# L6790A_Si.net
KiCad netlist of a schematic drawn in Altium Designer
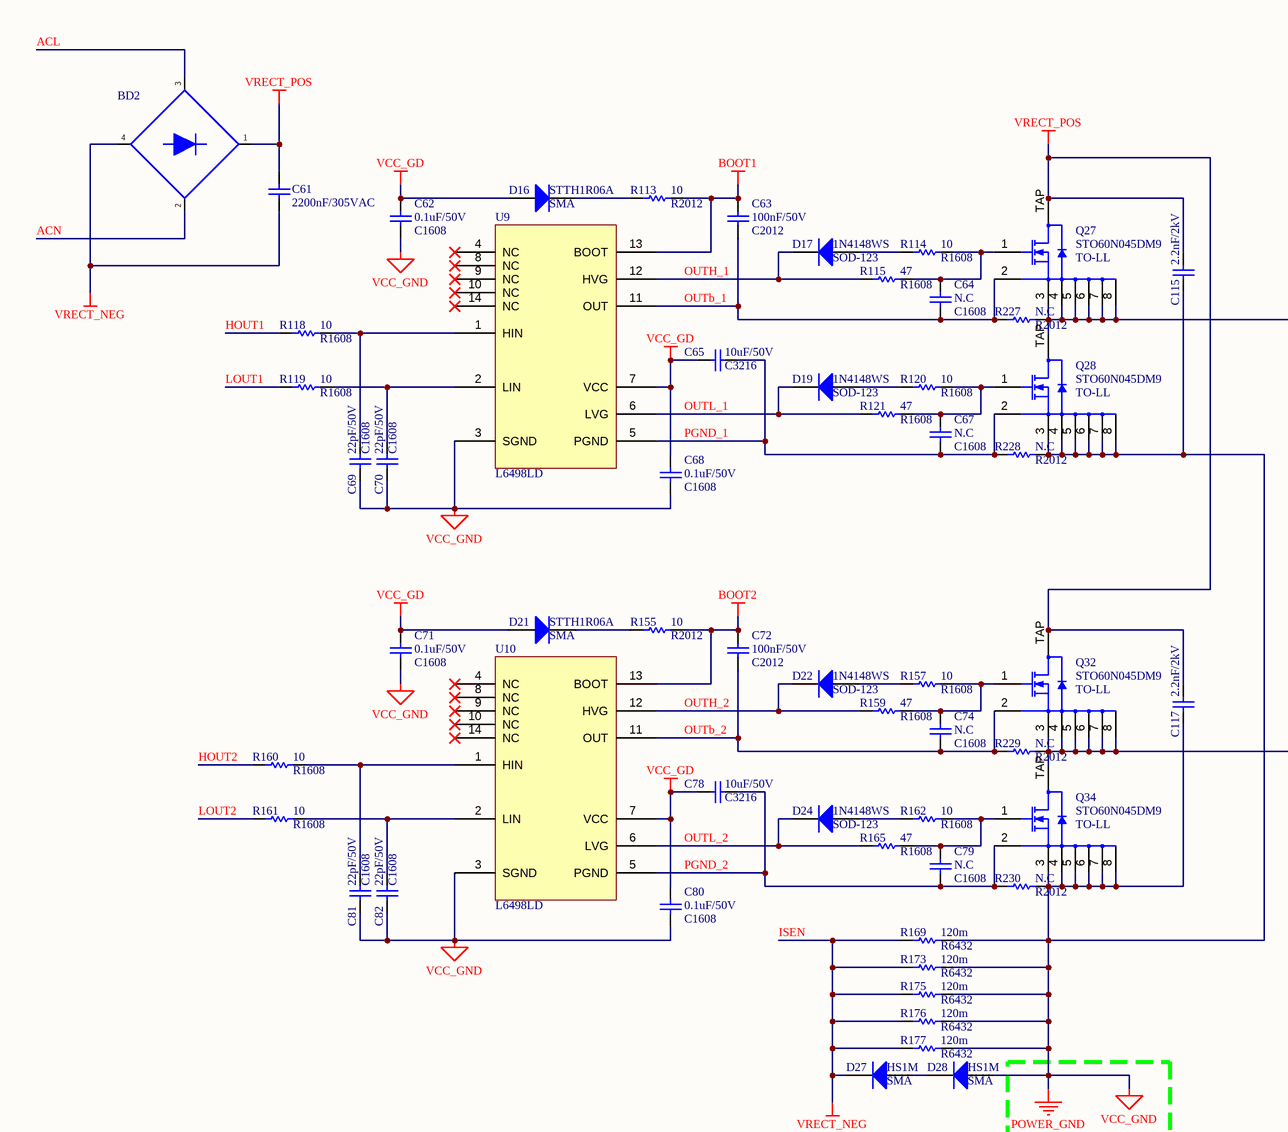
[diagram p0: L6790A_Si.SchDoc, top left]
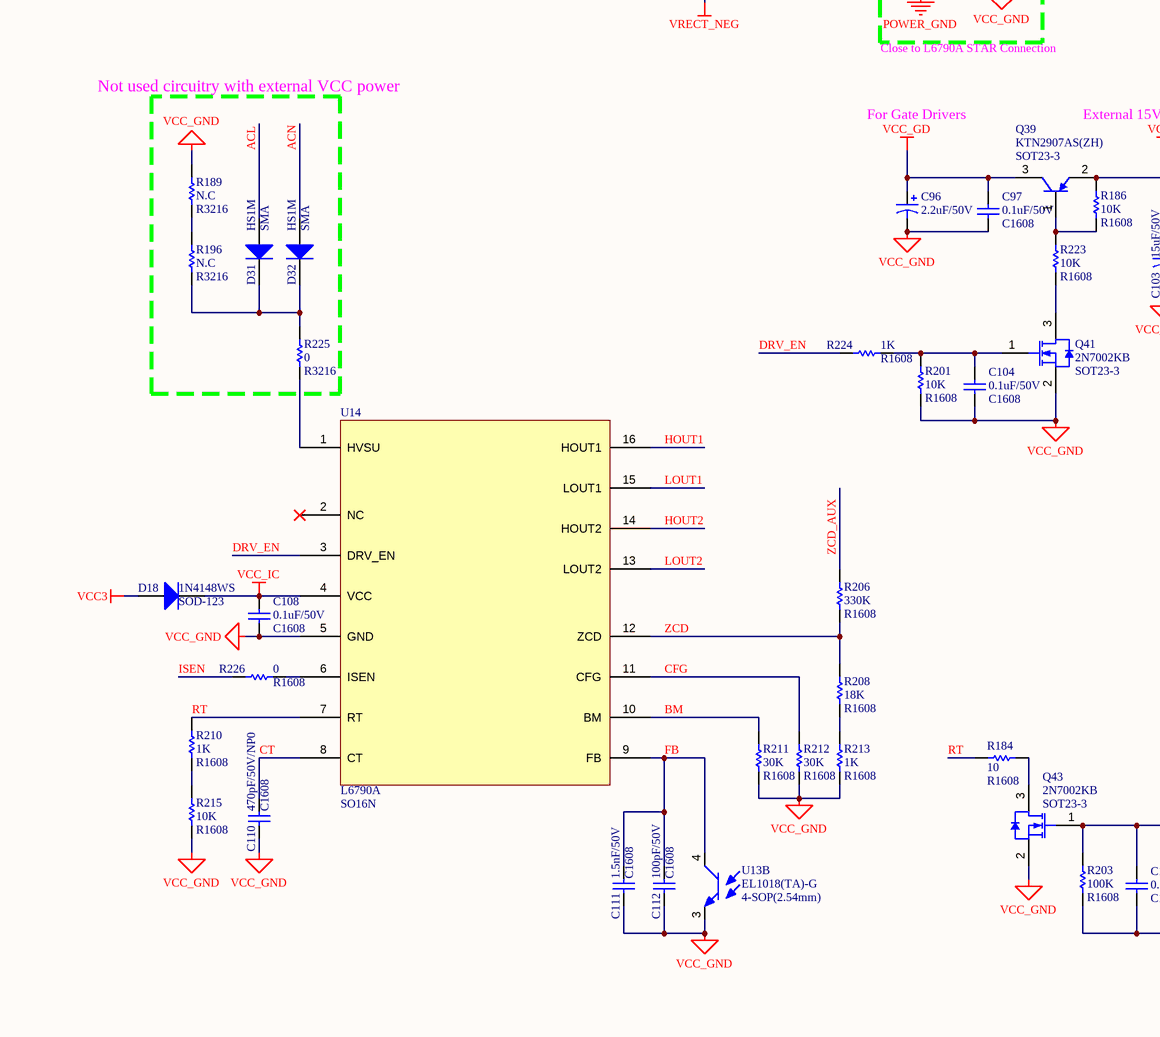
[diagram p1: L6790A_Si.SchDoc, bottom left]
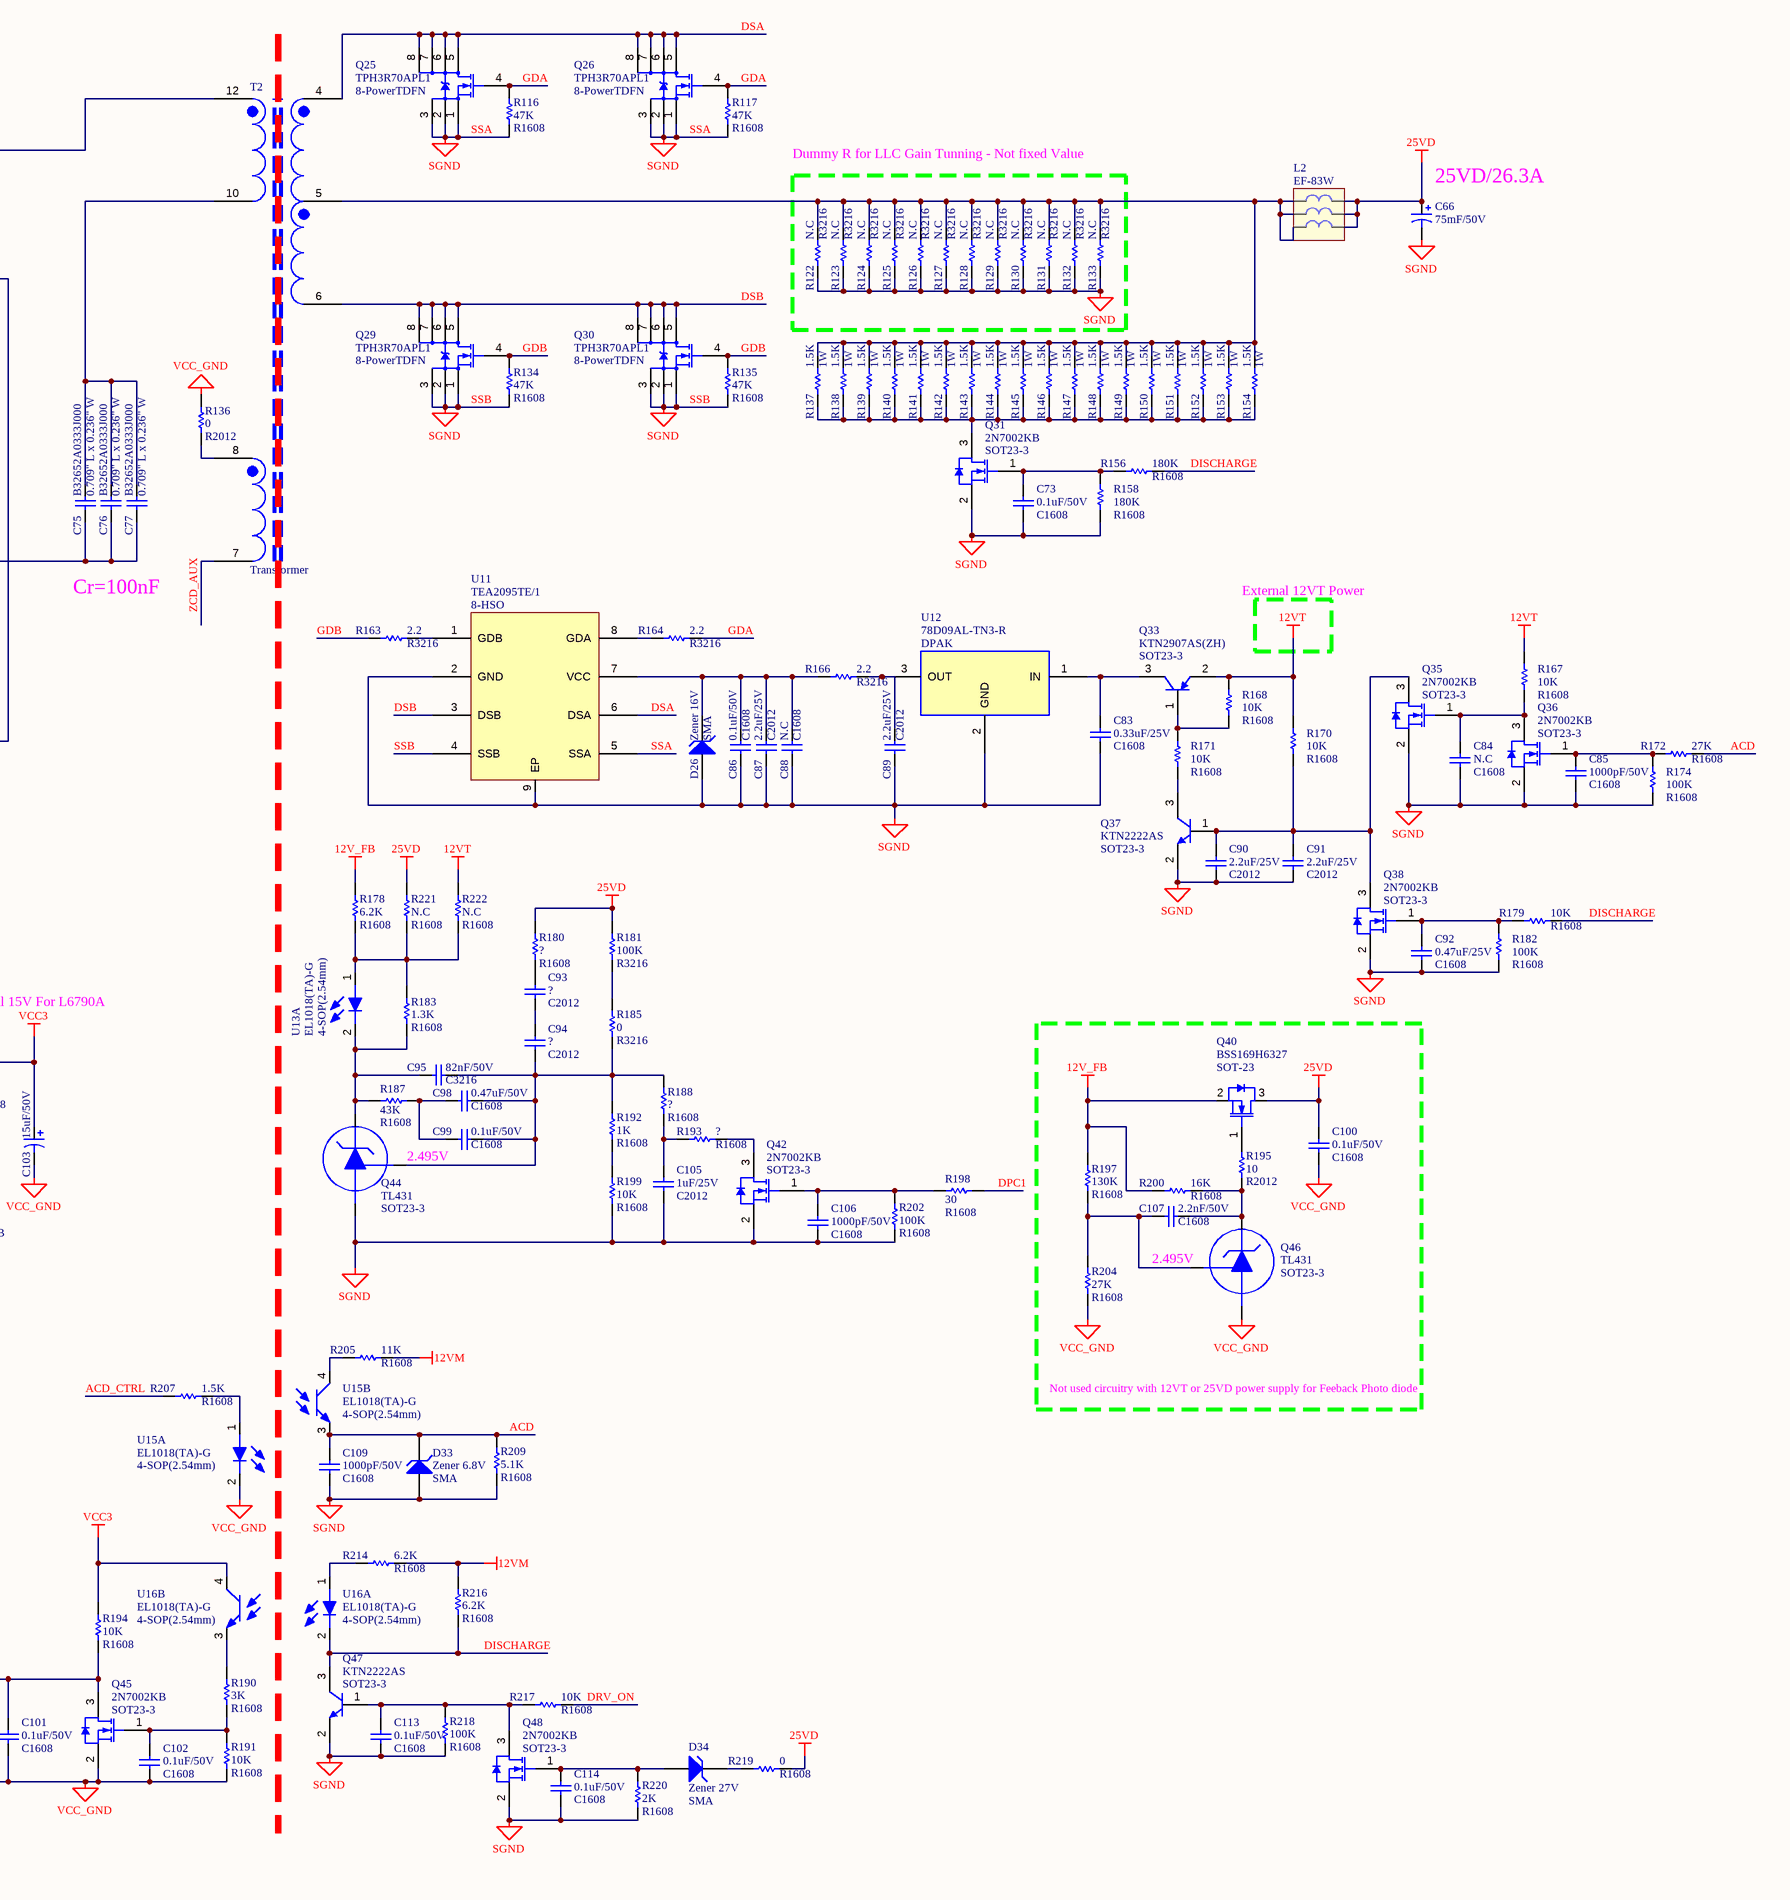
[diagram p2: L6790A_Si.SchDoc, bottom right]

(export (version "E")
  (design (tool "Eeschema 10.0.6"))
  (components
    (comp (ref "BD2")
      (value "TS6KL60")
      (footprint "2W-DIO-MI-4L-4_6X25X15-7_5P-BD")
      (description "BRIDGE DIODE")
      (libsource (lib "Schematic") (part "BRIDGE"))
    )
    (comp (ref "C61")
      (value "2200nF/305VAC")
      (description "Chip MLCC")
      (libsource (lib "Miscellaneous Devices") (part "Cap"))
    )
    (comp (ref "C62")
      (value "0.1uF/50V")
      (description "Chip MLCC")
      (fields (field (name "PACKAGE/CASE") "C1608"))
      (libsource (lib "Miscellaneous Devices") (part "Cap"))
    )
    (comp (ref "C63")
      (value "100nF/50V")
      (description "Chip MLCC")
      (fields (field (name "PACKAGE/CASE") "C2012"))
      (libsource (lib "Miscellaneous Devices") (part "Cap"))
    )
    (comp (ref "C64")
      (value "N.C")
      (description "Chip MLCC")
      (fields (field (name "PACKAGE/CASE") "C1608"))
      (libsource (lib "Miscellaneous Devices") (part "Cap"))
    )
    (comp (ref "C65")
      (value "10uF/50V")
      (description "Chip MLCC")
      (fields (field (name "PACKAGE/CASE") "C3216"))
      (libsource (lib "Miscellaneous Devices") (part "Cap"))
    )
    (comp (ref "C66")
      (value "75mF/50V")
      (footprint "1W-CAP-MI-2L-16DX25-7_5P-EL-F-R1212")
      (description "Electrolytic Capacitor")
      (libsource (lib "Miscellaneous Devices") (part "Cap Pol1"))
    )
    (comp (ref "C67")
      (value "N.C")
      (description "Chip MLCC")
      (fields (field (name "PACKAGE/CASE") "C1608"))
      (libsource (lib "Miscellaneous Devices") (part "Cap"))
    )
    (comp (ref "C68")
      (value "0.1uF/50V")
      (description "Chip MLCC")
      (fields (field (name "PACKAGE/CASE") "C1608"))
      (libsource (lib "Miscellaneous Devices") (part "Cap"))
    )
    (comp (ref "C69")
      (value "22pF/50V")
      (description "Chip MLCC")
      (fields (field (name "PACKAGE/CASE") "C1608"))
      (libsource (lib "Miscellaneous Devices") (part "Cap"))
    )
    (comp (ref "C70")
      (value "22pF/50V")
      (description "Chip MLCC")
      (fields (field (name "PACKAGE/CASE") "C1608"))
      (libsource (lib "Miscellaneous Devices") (part "Cap"))
    )
    (comp (ref "C71")
      (value "0.1uF/50V")
      (description "Chip MLCC")
      (fields (field (name "PACKAGE/CASE") "C1608"))
      (libsource (lib "Miscellaneous Devices") (part "Cap"))
    )
    (comp (ref "C72")
      (value "100nF/50V")
      (description "Chip MLCC")
      (fields (field (name "PACKAGE/CASE") "C2012"))
      (libsource (lib "Miscellaneous Devices") (part "Cap"))
    )
    (comp (ref "C73")
      (value "0.1uF/50V")
      (description "Chip MLCC")
      (fields (field (name "PACKAGE/CASE") "C1608"))
      (libsource (lib "Miscellaneous Devices") (part "Cap"))
    )
    (comp (ref "C74")
      (value "N.C")
      (description "Chip MLCC")
      (fields (field (name "PACKAGE/CASE") "C1608"))
      (libsource (lib "Miscellaneous Devices") (part "Cap"))
    )
    (comp (ref "C75")
      (value "B32652A0333J000")
      (description "Chip MLCC")
      (fields (field (name "PACKAGE/CASE") "0.709\" L x 0.236\" W"))
      (libsource (lib "Miscellaneous Devices") (part "Cap"))
    )
    (comp (ref "C76")
      (value "B32652A0333J000")
      (description "Chip MLCC")
      (fields (field (name "PACKAGE/CASE") "0.709\" L x 0.236\" W"))
      (libsource (lib "Miscellaneous Devices") (part "Cap"))
    )
    (comp (ref "C77")
      (value "B32652A0333J000")
      (description "Chip MLCC")
      (fields (field (name "PACKAGE/CASE") "0.709\" L x 0.236\" W"))
      (libsource (lib "Miscellaneous Devices") (part "Cap"))
    )
    (comp (ref "C78")
      (value "10uF/50V")
      (description "Chip MLCC")
      (fields (field (name "PACKAGE/CASE") "C3216"))
      (libsource (lib "Miscellaneous Devices") (part "Cap"))
    )
    (comp (ref "C79")
      (value "N.C")
      (description "Chip MLCC")
      (fields (field (name "PACKAGE/CASE") "C1608"))
      (libsource (lib "Miscellaneous Devices") (part "Cap"))
    )
    (comp (ref "C80")
      (value "0.1uF/50V")
      (description "Chip MLCC")
      (fields (field (name "PACKAGE/CASE") "C1608"))
      (libsource (lib "Miscellaneous Devices") (part "Cap"))
    )
    (comp (ref "C81")
      (value "22pF/50V")
      (description "Chip MLCC")
      (fields (field (name "PACKAGE/CASE") "C1608"))
      (libsource (lib "Miscellaneous Devices") (part "Cap"))
    )
    (comp (ref "C82")
      (value "22pF/50V")
      (description "Chip MLCC")
      (fields (field (name "PACKAGE/CASE") "C1608"))
      (libsource (lib "Miscellaneous Devices") (part "Cap"))
    )
    (comp (ref "C83")
      (value "0.33uF/25V")
      (description "Chip MLCC")
      (fields (field (name "PACKAGE/CASE") "C1608"))
      (libsource (lib "Miscellaneous Devices") (part "Cap"))
    )
    (comp (ref "C84")
      (value "N.C")
      (description "Chip MLCC")
      (fields (field (name "PACKAGE/CASE") "C1608"))
      (libsource (lib "Miscellaneous Devices") (part "Cap"))
    )
    (comp (ref "C85")
      (value "1000pF/50V")
      (description "Chip MLCC")
      (fields (field (name "PACKAGE/CASE") "C1608"))
      (libsource (lib "Miscellaneous Devices") (part "Cap"))
    )
    (comp (ref "C86")
      (value "0.1uF/50V")
      (description "Chip MLCC")
      (fields (field (name "PACKAGE/CASE") "C1608"))
      (libsource (lib "Miscellaneous Devices") (part "Cap"))
    )
    (comp (ref "C87")
      (value "2.2uF/25V")
      (description "Chip MLCC")
      (fields (field (name "PACKAGE/CASE") "C2012"))
      (libsource (lib "Miscellaneous Devices") (part "Cap"))
    )
    (comp (ref "C88")
      (value "N.C")
      (description "Chip MLCC")
      (fields (field (name "PACKAGE/CASE") "C1608"))
      (libsource (lib "Miscellaneous Devices") (part "Cap"))
    )
    (comp (ref "C89")
      (value "2.2uF/25V")
      (description "Chip MLCC")
      (fields (field (name "PACKAGE/CASE") "C2012"))
      (libsource (lib "Miscellaneous Devices") (part "Cap"))
    )
    (comp (ref "C90")
      (value "2.2uF/25V")
      (description "Chip MLCC")
      (fields (field (name "PACKAGE/CASE") "C2012"))
      (libsource (lib "Miscellaneous Devices") (part "Cap"))
    )
    (comp (ref "C91")
      (value "2.2uF/25V")
      (description "Chip MLCC")
      (fields (field (name "PACKAGE/CASE") "C2012"))
      (libsource (lib "Miscellaneous Devices") (part "Cap"))
    )
    (comp (ref "C92")
      (value "0.47uF/25V")
      (description "Chip MLCC")
      (fields (field (name "PACKAGE/CASE") "C1608"))
      (libsource (lib "Miscellaneous Devices") (part "Cap"))
    )
    (comp (ref "C93")
      (value "?")
      (description "Chip MLCC")
      (fields (field (name "PACKAGE/CASE") "C2012"))
      (libsource (lib "Miscellaneous Devices") (part "Cap"))
    )
    (comp (ref "C94")
      (value "?")
      (description "Chip MLCC")
      (fields (field (name "PACKAGE/CASE") "C2012"))
      (libsource (lib "Miscellaneous Devices") (part "Cap"))
    )
    (comp (ref "C95")
      (value "82nF/50V")
      (footprint "LGP55B_25U1_Y2S:CAP-CHP-3216-R0")
      (description "Chip MLCC")
      (fields (field (name "PACKAGE/CASE") "C3216"))
      (libsource (lib "Miscellaneous Devices") (part "Cap"))
    )
    (comp (ref "C96")
      (value "2.2uF/50V")
      (footprint "CAP-RA-D5.0H12_5-P2-R0CA")
      (description "Electrolytic Capacitor 33uF/25V")
      (libsource (lib "Miscellaneous Devices") (part "Cap Pol1"))
    )
    (comp (ref "C97")
      (value "0.1uF/50V")
      (description "Chip MLCC")
      (fields (field (name "PACKAGE/CASE") "C1608"))
      (libsource (lib "Miscellaneous Devices") (part "Cap"))
    )
    (comp (ref "C98")
      (value "0.47uF/50V")
      (description "Chip MLCC")
      (fields (field (name "PACKAGE/CASE") "C1608"))
      (libsource (lib "Miscellaneous Devices") (part "Cap"))
    )
    (comp (ref "C99")
      (value "0.1uF/50V")
      (description "Chip MLCC")
      (fields (field (name "PACKAGE/CASE") "C1608"))
      (libsource (lib "Miscellaneous Devices") (part "Cap"))
    )
    (comp (ref "C100")
      (value "0.1uF/50V")
      (description "Chip MLCC")
      (fields (field (name "PACKAGE/CASE") "C1608"))
      (libsource (lib "Miscellaneous Devices") (part "Cap"))
    )
    (comp (ref "C101")
      (value "0.1uF/50V")
      (description "Chip MLCC")
      (fields (field (name "PACKAGE/CASE") "C1608"))
      (libsource (lib "Miscellaneous Devices") (part "Cap"))
    )
    (comp (ref "C102")
      (value "0.1uF/50V")
      (description "Chip MLCC")
      (fields (field (name "PACKAGE/CASE") "C1608"))
      (libsource (lib "Miscellaneous Devices") (part "Cap"))
    )
    (comp (ref "C103")
      (value "15uF/50V")
      (footprint "CAP-RA-D5.0H12_5-P2-R0CA")
      (description "Electrolytic Capacitor 33uF/25V")
      (libsource (lib "Miscellaneous Devices") (part "Cap Pol1"))
    )
    (comp (ref "C104")
      (value "0.1uF/50V")
      (description "Chip MLCC")
      (fields (field (name "PACKAGE/CASE") "C1608"))
      (libsource (lib "Miscellaneous Devices") (part "Cap"))
    )
    (comp (ref "C105")
      (value "1uF/25V")
      (description "Chip MLCC")
      (fields (field (name "PACKAGE/CASE") "C2012"))
      (libsource (lib "Miscellaneous Devices") (part "Cap"))
    )
    (comp (ref "C106")
      (value "1000pF/50V")
      (description "Chip MLCC")
      (fields (field (name "PACKAGE/CASE") "C1608"))
      (libsource (lib "Miscellaneous Devices") (part "Cap"))
    )
    (comp (ref "C107")
      (value "2.2nF/50V")
      (description "Chip MLCC")
      (fields (field (name "PACKAGE/CASE") "C1608"))
      (libsource (lib "Miscellaneous Devices") (part "Cap"))
    )
    (comp (ref "C108")
      (value "0.1uF/50V")
      (description "Chip MLCC")
      (fields (field (name "PACKAGE/CASE") "C1608"))
      (libsource (lib "Miscellaneous Devices") (part "Cap"))
    )
    (comp (ref "C109")
      (value "1000pF/50V")
      (description "Chip MLCC")
      (fields (field (name "PACKAGE/CASE") "C1608"))
      (libsource (lib "Miscellaneous Devices") (part "Cap"))
    )
    (comp (ref "C110")
      (value "470pF/50V/NP0")
      (description "Chip MLCC")
      (fields (field (name "PACKAGE/CASE") "C1608"))
      (libsource (lib "Miscellaneous Devices") (part "Cap"))
    )
    (comp (ref "C111")
      (value "1.5nF/50V")
      (description "Chip MLCC")
      (fields (field (name "PACKAGE/CASE") "C1608"))
      (libsource (lib "Miscellaneous Devices") (part "Cap"))
    )
    (comp (ref "C112")
      (value "100pF/50V")
      (description "Chip MLCC")
      (fields (field (name "PACKAGE/CASE") "C1608"))
      (libsource (lib "Miscellaneous Devices") (part "Cap"))
    )
    (comp (ref "C113")
      (value "0.1uF/50V")
      (description "Chip MLCC")
      (fields (field (name "PACKAGE/CASE") "C1608"))
      (libsource (lib "Miscellaneous Devices") (part "Cap"))
    )
    (comp (ref "C114")
      (value "0.1uF/50V")
      (description "Chip MLCC")
      (fields (field (name "PACKAGE/CASE") "C1608"))
      (libsource (lib "Miscellaneous Devices") (part "Cap"))
    )
    (comp (ref "C115")
      (value "2.2nF/2kV")
      (description "Chip MLCC")
      (libsource (lib "Miscellaneous Devices") (part "Cap"))
    )
    (comp (ref "C117")
      (value "2.2nF/2kV")
      (description "Chip MLCC")
      (libsource (lib "Miscellaneous Devices") (part "Cap"))
    )
    (comp (ref "D16")
      (value "STTH1R06A")
      (footprint "DIO-SOD123")
      (description "DIODE SCHOTTKY 30V 200MA SOD123")
      (fields (field (name "PACKAGE/CASE") "SMA"))
      (libsource (lib "Miscellaneous Devices") (part "Diode 1N4148"))
    )
    (comp (ref "D17")
      (value "1N4148WS")
      (footprint "DIO-SOD123")
      (description "DIODE SCHOTTKY 30V 200MA SOD123")
      (fields (field (name "PACKAGE/CASE") "SOD-123"))
      (libsource (lib "Miscellaneous Devices") (part "Diode 1N4148"))
    )
    (comp (ref "D18")
      (value "1N4148WS")
      (footprint "DIO-SOD123")
      (description "DIODE SCHOTTKY 30V 200MA SOD123")
      (fields (field (name "PACKAGE/CASE") "SOD-123"))
      (libsource (lib "Miscellaneous Devices") (part "Diode 1N4148"))
    )
    (comp (ref "D19")
      (value "1N4148WS")
      (footprint "DIO-SOD123")
      (description "DIODE SCHOTTKY 30V 200MA SOD123")
      (fields (field (name "PACKAGE/CASE") "SOD-123"))
      (libsource (lib "Miscellaneous Devices") (part "Diode 1N4148"))
    )
    (comp (ref "D21")
      (value "STTH1R06A")
      (footprint "DIO-SOD123")
      (description "DIODE SCHOTTKY 30V 200MA SOD123")
      (fields (field (name "PACKAGE/CASE") "SMA"))
      (libsource (lib "Miscellaneous Devices") (part "Diode 1N4148"))
    )
    (comp (ref "D22")
      (value "1N4148WS")
      (footprint "DIO-SOD123")
      (description "DIODE SCHOTTKY 30V 200MA SOD123")
      (fields (field (name "PACKAGE/CASE") "SOD-123"))
      (libsource (lib "Miscellaneous Devices") (part "Diode 1N4148"))
    )
    (comp (ref "D24")
      (value "1N4148WS")
      (footprint "DIO-SOD123")
      (description "DIODE SCHOTTKY 30V 200MA SOD123")
      (fields (field (name "PACKAGE/CASE") "SOD-123"))
      (libsource (lib "Miscellaneous Devices") (part "Diode 1N4148"))
    )
    (comp (ref "D26")
      (value "Zener 16V")
      (footprint "1W-DIO-CHP-2L-SOD106-SMA")
      (description "DIODE ZENER 30V 1W DO214AC")
      (fields (field (name "PACKAGE/CASE") "SMA"))
      (libsource (lib "Miscellaneous Devices") (part "D Zener"))
    )
    (comp (ref "D27")
      (value "HS1M")
      (footprint "DIO-SOD123")
      (description "DIODE SCHOTTKY 30V 200MA SOD123")
      (fields (field (name "PACKAGE/CASE") "SMA"))
      (libsource (lib "Miscellaneous Devices") (part "Diode 1N4148"))
    )
    (comp (ref "D28")
      (value "HS1M")
      (footprint "DIO-SOD123")
      (description "DIODE SCHOTTKY 30V 200MA SOD123")
      (fields (field (name "PACKAGE/CASE") "SMA"))
      (libsource (lib "Miscellaneous Devices") (part "Diode 1N4148"))
    )
    (comp (ref "D31")
      (value "HS1M")
      (footprint "DIO-SOD123")
      (description "DIODE SCHOTTKY 30V 200MA SOD123")
      (fields (field (name "PACKAGE/CASE") "SMA"))
      (libsource (lib "Miscellaneous Devices") (part "Diode 1N4148"))
    )
    (comp (ref "D32")
      (value "HS1M")
      (footprint "DIO-SOD123")
      (description "DIODE SCHOTTKY 30V 200MA SOD123")
      (fields (field (name "PACKAGE/CASE") "SMA"))
      (libsource (lib "Miscellaneous Devices") (part "Diode 1N4148"))
    )
    (comp (ref "D33")
      (value "Zener 6.8V")
      (footprint "1W-DIO-CHP-2L-SOD106-SMA")
      (description "DIODE ZENER 30V 1W DO214AC")
      (fields (field (name "PACKAGE/CASE") "SMA"))
      (libsource (lib "Miscellaneous Devices") (part "D Zener"))
    )
    (comp (ref "D34")
      (value "Zener 27V")
      (footprint "1W-DIO-CHP-2L-SOD106-SMA")
      (description "DIODE ZENER 30V 1W DO214AC")
      (fields (field (name "PACKAGE/CASE") "SMA"))
      (libsource (lib "Miscellaneous Devices") (part "D Zener"))
    )
    (comp (ref "L2") (value "EF-83W") (libsource (lib "Schematic") (part "EF-83W")))
    (comp (ref "Q25")
      (value "TPH3R70APL1")
      (description "N-Channel 100 V 90A (Tc) 210W (Tc) Surface Mount 8-SOP Advance (5x5.75)")
      (fields (field (name "PACKAGE/CASE") "8-PowerTDFN"))
      (libsource (lib "Schematic") (part "TPH3R70APL1"))
    )
    (comp (ref "Q26")
      (value "TPH3R70APL1")
      (description "N-Channel 100 V 90A (Tc) 210W (Tc) Surface Mount 8-SOP Advance (5x5.75)")
      (fields (field (name "PACKAGE/CASE") "8-PowerTDFN"))
      (libsource (lib "Schematic") (part "TPH3R70APL1"))
    )
    (comp (ref "Q27")
      (value "STO60N045DM9")
      (description "N‑channel 600 V, 35 mΩ typ., 56 A MDmesh DM9 Power MOSFET in a TO‑LL package")
      (fields (field (name "PACKAGE/CASE") "TO-LL"))
      (libsource (lib "Schematic") (part "STO60N045DM9"))
    )
    (comp (ref "Q28")
      (value "STO60N045DM9")
      (description "N‑channel 600 V, 35 mΩ typ., 56 A MDmesh DM9 Power MOSFET in a TO‑LL package")
      (fields (field (name "PACKAGE/CASE") "TO-LL"))
      (libsource (lib "Schematic") (part "STO60N045DM9"))
    )
    (comp (ref "Q29")
      (value "TPH3R70APL1")
      (description "N-Channel 100 V 90A (Tc) 210W (Tc) Surface Mount 8-SOP Advance (5x5.75)")
      (fields (field (name "PACKAGE/CASE") "8-PowerTDFN"))
      (libsource (lib "Schematic") (part "TPH3R70APL1"))
    )
    (comp (ref "Q30")
      (value "TPH3R70APL1")
      (description "N-Channel 100 V 90A (Tc) 210W (Tc) Surface Mount 8-SOP Advance (5x5.75)")
      (fields (field (name "PACKAGE/CASE") "8-PowerTDFN"))
      (libsource (lib "Schematic") (part "TPH3R70APL1"))
    )
    (comp (ref "Q31")
      (value "2N7002KB")
      (description "N-CH MOSFET")
      (fields (field (name "PACKAGE/CASE") "SOT23-3"))
      (libsource (lib "Schematic") (part "2N7002KB"))
    )
    (comp (ref "Q32")
      (value "STO60N045DM9")
      (description "N‑channel 600 V, 35 mΩ typ., 56 A MDmesh DM9 Power MOSFET in a TO‑LL package")
      (fields (field (name "PACKAGE/CASE") "TO-LL"))
      (libsource (lib "Schematic") (part "STO60N045DM9"))
    )
    (comp (ref "Q33")
      (value "KTN2907AS(ZH)")
      (description "PNP BJT")
      (fields (field (name "PACKAGE/CASE") "SOT23-3"))
      (libsource (lib "Schematic") (part "ONSC-PNP-B1E2C3-3"))
    )
    (comp (ref "Q34")
      (value "STO60N045DM9")
      (description "N‑channel 600 V, 35 mΩ typ., 56 A MDmesh DM9 Power MOSFET in a TO‑LL package")
      (fields (field (name "PACKAGE/CASE") "TO-LL"))
      (libsource (lib "Schematic") (part "STO60N045DM9"))
    )
    (comp (ref "Q35")
      (value "2N7002KB")
      (description "N-CH MOSFET")
      (fields (field (name "PACKAGE/CASE") "SOT23-3"))
      (libsource (lib "Schematic") (part "2N7002KB"))
    )
    (comp (ref "Q36")
      (value "2N7002KB")
      (description "N-CH MOSFET")
      (fields (field (name "PACKAGE/CASE") "SOT23-3"))
      (libsource (lib "Schematic") (part "2N7002KB"))
    )
    (comp (ref "Q37")
      (value "KTN2222AS")
      (description "BJT NPN")
      (fields (field (name "PACKAGE/CASE") "SOT23-3"))
      (libsource (lib "Schematic") (part "ONSC-NPN-B1E2C3-3"))
    )
    (comp (ref "Q38")
      (value "2N7002KB")
      (description "N-CH MOSFET")
      (fields (field (name "PACKAGE/CASE") "SOT23-3"))
      (libsource (lib "Schematic") (part "2N7002KB"))
    )
    (comp (ref "Q39")
      (value "KTN2907AS(ZH)")
      (description "PNP BJT")
      (fields (field (name "PACKAGE/CASE") "SOT23-3"))
      (libsource (lib "Schematic") (part "ONSC-PNP-B1E2C3-3"))
    )
    (comp (ref "Q40")
      (value "BSS169H6327")
      (footprint "SOT-23_TR")
      (description "MOSFET N-CH 100V 170MA SOT23-3")
      (fields (field (name "PACKAGE/CASE") "SOT-23"))
      (libsource (lib "Miscellaneous Devices") (part "CMP-32901-000982-1"))
    )
    (comp (ref "Q41")
      (value "2N7002KB")
      (description "N-CH MOSFET")
      (fields (field (name "PACKAGE/CASE") "SOT23-3"))
      (libsource (lib "Schematic") (part "2N7002KB"))
    )
    (comp (ref "Q42")
      (value "2N7002KB")
      (description "N-CH MOSFET")
      (fields (field (name "PACKAGE/CASE") "SOT23-3"))
      (libsource (lib "Schematic") (part "2N7002KB"))
    )
    (comp (ref "Q43")
      (value "2N7002KB")
      (description "N-CH MOSFET")
      (fields (field (name "PACKAGE/CASE") "SOT23-3"))
      (libsource (lib "Schematic") (part "2N7002KB"))
    )
    (comp (ref "Q44")
      (value "TL431")
      (footprint "SOT-23_TR")
      (description "IC VREF SHUNT ADJ 1% SOT23-3")
      (fields (field (name "PACKAGE/CASE") "SOT23-3"))
      (libsource (lib "*") (part "1W-IC-CHP-3L-SOT23-SCR-R0"))
    )
    (comp (ref "Q45")
      (value "2N7002KB")
      (description "N-CH MOSFET")
      (fields (field (name "PACKAGE/CASE") "SOT23-3"))
      (libsource (lib "Schematic") (part "2N7002KB"))
    )
    (comp (ref "Q46")
      (value "TL431")
      (footprint "SOT-23_TR")
      (description "IC VREF SHUNT ADJ 1% SOT23-3")
      (fields (field (name "PACKAGE/CASE") "SOT23-3"))
      (libsource (lib "*") (part "1W-IC-CHP-3L-SOT23-SCR-R0"))
    )
    (comp (ref "Q47")
      (value "KTN2222AS")
      (description "BJT NPN")
      (fields (field (name "PACKAGE/CASE") "SOT23-3"))
      (libsource (lib "Schematic") (part "ONSC-NPN-B1E2C3-3"))
    )
    (comp (ref "Q48")
      (value "2N7002KB")
      (description "N-CH MOSFET")
      (fields (field (name "PACKAGE/CASE") "SOT23-3"))
      (libsource (lib "Schematic") (part "2N7002KB"))
    )
    (comp (ref "R113")
      (value "10")
      (footprint "RES-1608")
      (description "Chip Resistor")
      (fields (field (name "PACKAGE/CASE") "R2012"))
      (libsource (lib "Miscellaneous Devices") (part "Res1"))
    )
    (comp (ref "R114")
      (value "10")
      (footprint "RES-1608")
      (description "Chip Resistor")
      (fields (field (name "PACKAGE/CASE") "R1608"))
      (libsource (lib "Miscellaneous Devices") (part "Res1"))
    )
    (comp (ref "R115")
      (value "47")
      (footprint "RES-1608")
      (description "Chip Resistor")
      (fields (field (name "PACKAGE/CASE") "R1608"))
      (libsource (lib "Miscellaneous Devices") (part "Res1"))
    )
    (comp (ref "R116")
      (value "47K")
      (footprint "RES-1608")
      (description "Chip Resistor")
      (fields (field (name "PACKAGE/CASE") "R1608"))
      (libsource (lib "Miscellaneous Devices") (part "Res1"))
    )
    (comp (ref "R117")
      (value "47K")
      (footprint "RES-1608")
      (description "Chip Resistor")
      (fields (field (name "PACKAGE/CASE") "R1608"))
      (libsource (lib "Miscellaneous Devices") (part "Res1"))
    )
    (comp (ref "R118")
      (value "10")
      (footprint "RES-1608")
      (description "Chip Resistor")
      (fields (field (name "PACKAGE/CASE") "R1608"))
      (libsource (lib "Miscellaneous Devices") (part "Res1"))
    )
    (comp (ref "R119")
      (value "10")
      (footprint "RES-1608")
      (description "Chip Resistor")
      (fields (field (name "PACKAGE/CASE") "R1608"))
      (libsource (lib "Miscellaneous Devices") (part "Res1"))
    )
    (comp (ref "R120")
      (value "10")
      (footprint "RES-1608")
      (description "Chip Resistor")
      (fields (field (name "PACKAGE/CASE") "R1608"))
      (libsource (lib "Miscellaneous Devices") (part "Res1"))
    )
    (comp (ref "R121")
      (value "47")
      (footprint "RES-1608")
      (description "Chip Resistor")
      (fields (field (name "PACKAGE/CASE") "R1608"))
      (libsource (lib "Miscellaneous Devices") (part "Res1"))
    )
    (comp (ref "R122")
      (value "N.C")
      (footprint "RES-3216")
      (description "Chip Resistor")
      (fields (field (name "PACKAGE/CASE") "R3216"))
      (libsource (lib "Miscellaneous Devices") (part "Res1"))
    )
    (comp (ref "R123")
      (value "N.C")
      (footprint "RES-3216")
      (description "Chip Resistor")
      (fields (field (name "PACKAGE/CASE") "R3216"))
      (libsource (lib "Miscellaneous Devices") (part "Res1"))
    )
    (comp (ref "R124")
      (value "N.C")
      (footprint "RES-3216")
      (description "Chip Resistor")
      (fields (field (name "PACKAGE/CASE") "R3216"))
      (libsource (lib "Miscellaneous Devices") (part "Res1"))
    )
    (comp (ref "R125")
      (value "N.C")
      (footprint "RES-3216")
      (description "Chip Resistor")
      (fields (field (name "PACKAGE/CASE") "R3216"))
      (libsource (lib "Miscellaneous Devices") (part "Res1"))
    )
    (comp (ref "R126")
      (value "N.C")
      (footprint "RES-3216")
      (description "Chip Resistor")
      (fields (field (name "PACKAGE/CASE") "R3216"))
      (libsource (lib "Miscellaneous Devices") (part "Res1"))
    )
    (comp (ref "R127")
      (value "N.C")
      (footprint "RES-3216")
      (description "Chip Resistor")
      (fields (field (name "PACKAGE/CASE") "R3216"))
      (libsource (lib "Miscellaneous Devices") (part "Res1"))
    )
    (comp (ref "R128")
      (value "N.C")
      (footprint "RES-3216")
      (description "Chip Resistor")
      (fields (field (name "PACKAGE/CASE") "R3216"))
      (libsource (lib "Miscellaneous Devices") (part "Res1"))
    )
    (comp (ref "R129")
      (value "N.C")
      (footprint "RES-3216")
      (description "Chip Resistor")
      (fields (field (name "PACKAGE/CASE") "R3216"))
      (libsource (lib "Miscellaneous Devices") (part "Res1"))
    )
    (comp (ref "R130")
      (value "N.C")
      (footprint "RES-3216")
      (description "Chip Resistor")
      (fields (field (name "PACKAGE/CASE") "R3216"))
      (libsource (lib "Miscellaneous Devices") (part "Res1"))
    )
    (comp (ref "R131")
      (value "N.C")
      (footprint "RES-3216")
      (description "Chip Resistor")
      (fields (field (name "PACKAGE/CASE") "R3216"))
      (libsource (lib "Miscellaneous Devices") (part "Res1"))
    )
    (comp (ref "R132")
      (value "N.C")
      (footprint "RES-3216")
      (description "Chip Resistor")
      (fields (field (name "PACKAGE/CASE") "R3216"))
      (libsource (lib "Miscellaneous Devices") (part "Res1"))
    )
    (comp (ref "R133")
      (value "N.C")
      (footprint "RES-3216")
      (description "Chip Resistor")
      (fields (field (name "PACKAGE/CASE") "R3216"))
      (libsource (lib "Miscellaneous Devices") (part "Res1"))
    )
    (comp (ref "R134")
      (value "47K")
      (footprint "RES-1608")
      (description "Chip Resistor")
      (fields (field (name "PACKAGE/CASE") "R1608"))
      (libsource (lib "Miscellaneous Devices") (part "Res1"))
    )
    (comp (ref "R135")
      (value "47K")
      (footprint "RES-1608")
      (description "Chip Resistor")
      (fields (field (name "PACKAGE/CASE") "R1608"))
      (libsource (lib "Miscellaneous Devices") (part "Res1"))
    )
    (comp (ref "R136")
      (value "0")
      (footprint "RES-1608")
      (description "Chip Resistor")
      (fields (field (name "PACKAGE/CASE") "R2012"))
      (libsource (lib "Miscellaneous Devices") (part "Res1"))
    )
    (comp (ref "R137")
      (value "1.5K")
      (description "Watt Resistor")
      (fields (field (name "PACKAGE/CASE") "1W"))
      (libsource (lib "Miscellaneous Devices") (part "Res1"))
    )
    (comp (ref "R138")
      (value "1.5K")
      (description "Watt Resistor")
      (fields (field (name "PACKAGE/CASE") "1W"))
      (libsource (lib "Miscellaneous Devices") (part "Res1"))
    )
    (comp (ref "R139")
      (value "1.5K")
      (description "Watt Resistor")
      (fields (field (name "PACKAGE/CASE") "1W"))
      (libsource (lib "Miscellaneous Devices") (part "Res1"))
    )
    (comp (ref "R140")
      (value "1.5K")
      (description "Watt Resistor")
      (fields (field (name "PACKAGE/CASE") "1W"))
      (libsource (lib "Miscellaneous Devices") (part "Res1"))
    )
    (comp (ref "R141")
      (value "1.5K")
      (description "Watt Resistor")
      (fields (field (name "PACKAGE/CASE") "1W"))
      (libsource (lib "Miscellaneous Devices") (part "Res1"))
    )
    (comp (ref "R142")
      (value "1.5K")
      (description "Watt Resistor")
      (fields (field (name "PACKAGE/CASE") "1W"))
      (libsource (lib "Miscellaneous Devices") (part "Res1"))
    )
    (comp (ref "R143")
      (value "1.5K")
      (description "Watt Resistor")
      (fields (field (name "PACKAGE/CASE") "1W"))
      (libsource (lib "Miscellaneous Devices") (part "Res1"))
    )
    (comp (ref "R144")
      (value "1.5K")
      (description "Watt Resistor")
      (fields (field (name "PACKAGE/CASE") "1W"))
      (libsource (lib "Miscellaneous Devices") (part "Res1"))
    )
    (comp (ref "R145")
      (value "1.5K")
      (description "Watt Resistor")
      (fields (field (name "PACKAGE/CASE") "1W"))
      (libsource (lib "Miscellaneous Devices") (part "Res1"))
    )
    (comp (ref "R146")
      (value "1.5K")
      (description "Watt Resistor")
      (fields (field (name "PACKAGE/CASE") "1W"))
      (libsource (lib "Miscellaneous Devices") (part "Res1"))
    )
    (comp (ref "R147")
      (value "1.5K")
      (description "Watt Resistor")
      (fields (field (name "PACKAGE/CASE") "1W"))
      (libsource (lib "Miscellaneous Devices") (part "Res1"))
    )
    (comp (ref "R148")
      (value "1.5K")
      (description "Watt Resistor")
      (fields (field (name "PACKAGE/CASE") "1W"))
      (libsource (lib "Miscellaneous Devices") (part "Res1"))
    )
    (comp (ref "R149")
      (value "1.5K")
      (description "Watt Resistor")
      (fields (field (name "PACKAGE/CASE") "1W"))
      (libsource (lib "Miscellaneous Devices") (part "Res1"))
    )
    (comp (ref "R150")
      (value "1.5K")
      (description "Watt Resistor")
      (fields (field (name "PACKAGE/CASE") "1W"))
      (libsource (lib "Miscellaneous Devices") (part "Res1"))
    )
    (comp (ref "R151")
      (value "1.5K")
      (description "Watt Resistor")
      (fields (field (name "PACKAGE/CASE") "1W"))
      (libsource (lib "Miscellaneous Devices") (part "Res1"))
    )
    (comp (ref "R152")
      (value "1.5K")
      (description "Watt Resistor")
      (fields (field (name "PACKAGE/CASE") "1W"))
      (libsource (lib "Miscellaneous Devices") (part "Res1"))
    )
    (comp (ref "R153")
      (value "1.5K")
      (description "Watt Resistor")
      (fields (field (name "PACKAGE/CASE") "1W"))
      (libsource (lib "Miscellaneous Devices") (part "Res1"))
    )
    (comp (ref "R154")
      (value "1.5K")
      (description "Watt Resistor")
      (fields (field (name "PACKAGE/CASE") "1W"))
      (libsource (lib "Miscellaneous Devices") (part "Res1"))
    )
    (comp (ref "R155")
      (value "10")
      (footprint "RES-1608")
      (description "Chip Resistor")
      (fields (field (name "PACKAGE/CASE") "R2012"))
      (libsource (lib "Miscellaneous Devices") (part "Res1"))
    )
    (comp (ref "R156")
      (value "180K")
      (footprint "RES-1608")
      (description "Chip Resistor")
      (fields (field (name "PACKAGE/CASE") "R1608"))
      (libsource (lib "Miscellaneous Devices") (part "Res1"))
    )
    (comp (ref "R157")
      (value "10")
      (footprint "RES-1608")
      (description "Chip Resistor")
      (fields (field (name "PACKAGE/CASE") "R1608"))
      (libsource (lib "Miscellaneous Devices") (part "Res1"))
    )
    (comp (ref "R158")
      (value "180K")
      (footprint "RES-1608")
      (description "Chip Resistor")
      (fields (field (name "PACKAGE/CASE") "R1608"))
      (libsource (lib "Miscellaneous Devices") (part "Res1"))
    )
    (comp (ref "R159")
      (value "47")
      (footprint "RES-1608")
      (description "Chip Resistor")
      (fields (field (name "PACKAGE/CASE") "R1608"))
      (libsource (lib "Miscellaneous Devices") (part "Res1"))
    )
    (comp (ref "R160")
      (value "10")
      (footprint "RES-1608")
      (description "Chip Resistor")
      (fields (field (name "PACKAGE/CASE") "R1608"))
      (libsource (lib "Miscellaneous Devices") (part "Res1"))
    )
    (comp (ref "R161")
      (value "10")
      (footprint "RES-1608")
      (description "Chip Resistor")
      (fields (field (name "PACKAGE/CASE") "R1608"))
      (libsource (lib "Miscellaneous Devices") (part "Res1"))
    )
    (comp (ref "R162")
      (value "10")
      (footprint "RES-1608")
      (description "Chip Resistor")
      (fields (field (name "PACKAGE/CASE") "R1608"))
      (libsource (lib "Miscellaneous Devices") (part "Res1"))
    )
    (comp (ref "R163")
      (value "2.2")
      (footprint "RES-3216")
      (description "Chip Resistor")
      (fields (field (name "PACKAGE/CASE") "R3216"))
      (libsource (lib "Miscellaneous Devices") (part "Res1"))
    )
    (comp (ref "R164")
      (value "2.2")
      (footprint "RES-3216")
      (description "Chip Resistor")
      (fields (field (name "PACKAGE/CASE") "R3216"))
      (libsource (lib "Miscellaneous Devices") (part "Res1"))
    )
    (comp (ref "R165")
      (value "47")
      (footprint "RES-1608")
      (description "Chip Resistor")
      (fields (field (name "PACKAGE/CASE") "R1608"))
      (libsource (lib "Miscellaneous Devices") (part "Res1"))
    )
    (comp (ref "R166")
      (value "2.2")
      (footprint "RES-3216")
      (description "Chip Resistor")
      (fields (field (name "PACKAGE/CASE") "R3216"))
      (libsource (lib "Miscellaneous Devices") (part "Res1"))
    )
    (comp (ref "R167")
      (value "10K")
      (footprint "RES-1608")
      (description "Chip Resistor")
      (fields (field (name "PACKAGE/CASE") "R1608"))
      (libsource (lib "Miscellaneous Devices") (part "Res1"))
    )
    (comp (ref "R168")
      (value "10K")
      (footprint "RES-1608")
      (description "Chip Resistor")
      (fields (field (name "PACKAGE/CASE") "R1608"))
      (libsource (lib "Miscellaneous Devices") (part "Res1"))
    )
    (comp (ref "R169")
      (value "120m")
      (description "Chip Resistor")
      (fields (field (name "PACKAGE/CASE") "R6432"))
      (libsource (lib "Miscellaneous Devices") (part "Res1"))
    )
    (comp (ref "R170")
      (value "10K")
      (footprint "RES-1608")
      (description "Chip Resistor")
      (fields (field (name "PACKAGE/CASE") "R1608"))
      (libsource (lib "Miscellaneous Devices") (part "Res1"))
    )
    (comp (ref "R171")
      (value "10K")
      (footprint "RES-1608")
      (description "Chip Resistor")
      (fields (field (name "PACKAGE/CASE") "R1608"))
      (libsource (lib "Miscellaneous Devices") (part "Res1"))
    )
    (comp (ref "R172")
      (value "27K")
      (footprint "RES-1608")
      (description "Chip Resistor")
      (fields (field (name "PACKAGE/CASE") "R1608"))
      (libsource (lib "Miscellaneous Devices") (part "Res1"))
    )
    (comp (ref "R173")
      (value "120m")
      (description "Chip Resistor")
      (fields (field (name "PACKAGE/CASE") "R6432"))
      (libsource (lib "Miscellaneous Devices") (part "Res1"))
    )
    (comp (ref "R174")
      (value "100K")
      (footprint "RES-1608")
      (description "Chip Resistor")
      (fields (field (name "PACKAGE/CASE") "R1608"))
      (libsource (lib "Miscellaneous Devices") (part "Res1"))
    )
    (comp (ref "R175")
      (value "120m")
      (description "Chip Resistor")
      (fields (field (name "PACKAGE/CASE") "R6432"))
      (libsource (lib "Miscellaneous Devices") (part "Res1"))
    )
    (comp (ref "R176")
      (value "120m")
      (description "Chip Resistor")
      (fields (field (name "PACKAGE/CASE") "R6432"))
      (libsource (lib "Miscellaneous Devices") (part "Res1"))
    )
    (comp (ref "R177")
      (value "120m")
      (description "Chip Resistor")
      (fields (field (name "PACKAGE/CASE") "R6432"))
      (libsource (lib "Miscellaneous Devices") (part "Res1"))
    )
    (comp (ref "R178")
      (value "6.2K")
      (footprint "RES-3216")
      (description "Chip Resistor")
      (fields (field (name "PACKAGE/CASE") "R1608"))
      (libsource (lib "Miscellaneous Devices") (part "Res1"))
    )
    (comp (ref "R179")
      (value "10K")
      (footprint "RES-1608")
      (description "Chip Resistor")
      (fields (field (name "PACKAGE/CASE") "R1608"))
      (libsource (lib "Miscellaneous Devices") (part "Res1"))
    )
    (comp (ref "R180")
      (value "?")
      (footprint "RES-1608")
      (description "Chip Resistor")
      (fields (field (name "PACKAGE/CASE") "R1608"))
      (libsource (lib "Miscellaneous Devices") (part "Res1"))
    )
    (comp (ref "R181")
      (value "100K")
      (footprint "RES-3216")
      (description "Chip Resistor")
      (fields (field (name "PACKAGE/CASE") "R3216"))
      (libsource (lib "Miscellaneous Devices") (part "Res1"))
    )
    (comp (ref "R182")
      (value "100K")
      (footprint "RES-1608")
      (description "Chip Resistor")
      (fields (field (name "PACKAGE/CASE") "R1608"))
      (libsource (lib "Miscellaneous Devices") (part "Res1"))
    )
    (comp (ref "R183")
      (value "1.3K")
      (footprint "RES-1608")
      (description "Chip Resistor")
      (fields (field (name "PACKAGE/CASE") "R1608"))
      (libsource (lib "Miscellaneous Devices") (part "Res1"))
    )
    (comp (ref "R184")
      (value "10")
      (footprint "RES-1608")
      (description "Chip Resistor")
      (fields (field (name "PACKAGE/CASE") "R1608"))
      (libsource (lib "Miscellaneous Devices") (part "Res1"))
    )
    (comp (ref "R185")
      (value "0")
      (footprint "RES-3216")
      (description "Chip Resistor")
      (fields (field (name "PACKAGE/CASE") "R3216"))
      (libsource (lib "Miscellaneous Devices") (part "Res1"))
    )
    (comp (ref "R186")
      (value "10K")
      (footprint "RES-1608")
      (description "Chip Resistor")
      (fields (field (name "PACKAGE/CASE") "R1608"))
      (libsource (lib "Miscellaneous Devices") (part "Res1"))
    )
    (comp (ref "R187")
      (value "43K")
      (footprint "RES-1608")
      (description "Chip Resistor")
      (fields (field (name "PACKAGE/CASE") "R1608"))
      (libsource (lib "Miscellaneous Devices") (part "Res1"))
    )
    (comp (ref "R188")
      (value "?")
      (footprint "RES-1608")
      (description "Chip Resistor")
      (fields (field (name "PACKAGE/CASE") "R1608"))
      (libsource (lib "Miscellaneous Devices") (part "Res1"))
    )
    (comp (ref "R189")
      (value "N.C")
      (footprint "RES-3216")
      (description "Chip Resistor")
      (fields (field (name "PACKAGE/CASE") "R3216"))
      (libsource (lib "Miscellaneous Devices") (part "Res1"))
    )
    (comp (ref "R190")
      (value "3K")
      (footprint "RES-1608")
      (description "Chip Resistor")
      (fields (field (name "PACKAGE/CASE") "R1608"))
      (libsource (lib "Miscellaneous Devices") (part "Res1"))
    )
    (comp (ref "R191")
      (value "10K")
      (footprint "RES-1608")
      (description "Chip Resistor")
      (fields (field (name "PACKAGE/CASE") "R1608"))
      (libsource (lib "Miscellaneous Devices") (part "Res1"))
    )
    (comp (ref "R192")
      (value "1K")
      (footprint "RES-1608")
      (description "Chip Resistor")
      (fields (field (name "PACKAGE/CASE") "R1608"))
      (libsource (lib "Miscellaneous Devices") (part "Res1"))
    )
    (comp (ref "R193")
      (value "?")
      (footprint "RES-1608")
      (description "Chip Resistor")
      (fields (field (name "PACKAGE/CASE") "R1608"))
      (libsource (lib "Miscellaneous Devices") (part "Res1"))
    )
    (comp (ref "R194")
      (value "10K")
      (footprint "RES-1608")
      (description "Chip Resistor")
      (fields (field (name "PACKAGE/CASE") "R1608"))
      (libsource (lib "Miscellaneous Devices") (part "Res1"))
    )
    (comp (ref "R195")
      (value "10")
      (footprint "RES-1608")
      (description "Chip Resistor")
      (fields (field (name "PACKAGE/CASE") "R2012"))
      (libsource (lib "Miscellaneous Devices") (part "Res1"))
    )
    (comp (ref "R196")
      (value "N.C")
      (footprint "RES-3216")
      (description "Chip Resistor")
      (fields (field (name "PACKAGE/CASE") "R3216"))
      (libsource (lib "Miscellaneous Devices") (part "Res1"))
    )
    (comp (ref "R197")
      (value "130K")
      (footprint "RES-1608")
      (description "Chip Resistor")
      (fields (field (name "PACKAGE/CASE") "R1608"))
      (libsource (lib "Miscellaneous Devices") (part "Res1"))
    )
    (comp (ref "R198")
      (value "30")
      (footprint "RES-1608")
      (description "Chip Resistor")
      (fields (field (name "PACKAGE/CASE") "R1608"))
      (libsource (lib "Miscellaneous Devices") (part "Res1"))
    )
    (comp (ref "R199")
      (value "10K")
      (footprint "RES-1608")
      (description "Chip Resistor")
      (fields (field (name "PACKAGE/CASE") "R1608"))
      (libsource (lib "Miscellaneous Devices") (part "Res1"))
    )
    (comp (ref "R200")
      (value "16K")
      (footprint "RES-1608")
      (description "Chip Resistor")
      (fields (field (name "PACKAGE/CASE") "R1608"))
      (libsource (lib "Miscellaneous Devices") (part "Res1"))
    )
    (comp (ref "R201")
      (value "10K")
      (footprint "RES-1608")
      (description "Chip Resistor")
      (fields (field (name "PACKAGE/CASE") "R1608"))
      (libsource (lib "Miscellaneous Devices") (part "Res1"))
    )
    (comp (ref "R202")
      (value "100K")
      (footprint "RES-1608")
      (description "Chip Resistor")
      (fields (field (name "PACKAGE/CASE") "R1608"))
      (libsource (lib "Miscellaneous Devices") (part "Res1"))
    )
    (comp (ref "R203")
      (value "100K")
      (footprint "RES-1608")
      (description "Chip Resistor")
      (fields (field (name "PACKAGE/CASE") "R1608"))
      (libsource (lib "Miscellaneous Devices") (part "Res1"))
    )
    (comp (ref "R204")
      (value "27K")
      (footprint "RES-1608")
      (description "Chip Resistor")
      (fields (field (name "PACKAGE/CASE") "R1608"))
      (libsource (lib "Miscellaneous Devices") (part "Res1"))
    )
    (comp (ref "R205")
      (value "11K")
      (footprint "RES-1608")
      (description "Chip Resistor")
      (fields (field (name "PACKAGE/CASE") "R1608"))
      (libsource (lib "Miscellaneous Devices") (part "Res1"))
    )
    (comp (ref "R206")
      (value "330K")
      (footprint "RES-1608")
      (description "Chip Resistor")
      (fields (field (name "PACKAGE/CASE") "R1608"))
      (libsource (lib "Miscellaneous Devices") (part "Res1"))
    )
    (comp (ref "R207")
      (value "1.5K")
      (footprint "RES-1608")
      (description "Chip Resistor")
      (fields (field (name "PACKAGE/CASE") "R1608"))
      (libsource (lib "Miscellaneous Devices") (part "Res1"))
    )
    (comp (ref "R208")
      (value "18K")
      (footprint "RES-1608")
      (description "Chip Resistor")
      (fields (field (name "PACKAGE/CASE") "R1608"))
      (libsource (lib "Miscellaneous Devices") (part "Res1"))
    )
    (comp (ref "R209")
      (value "5.1K")
      (footprint "RES-1608")
      (description "Chip Resistor")
      (fields (field (name "PACKAGE/CASE") "R1608"))
      (libsource (lib "Miscellaneous Devices") (part "Res1"))
    )
    (comp (ref "R210")
      (value "1K")
      (footprint "RES-1608")
      (description "Chip Resistor")
      (fields (field (name "PACKAGE/CASE") "R1608"))
      (libsource (lib "Miscellaneous Devices") (part "Res1"))
    )
    (comp (ref "R211")
      (value "30K")
      (footprint "RES-1608")
      (description "Chip Resistor")
      (fields (field (name "PACKAGE/CASE") "R1608"))
      (libsource (lib "Miscellaneous Devices") (part "Res1"))
    )
    (comp (ref "R212")
      (value "30K")
      (footprint "RES-1608")
      (description "Chip Resistor")
      (fields (field (name "PACKAGE/CASE") "R1608"))
      (libsource (lib "Miscellaneous Devices") (part "Res1"))
    )
    (comp (ref "R213")
      (value "1K")
      (footprint "RES-1608")
      (description "Chip Resistor")
      (fields (field (name "PACKAGE/CASE") "R1608"))
      (libsource (lib "Miscellaneous Devices") (part "Res1"))
    )
    (comp (ref "R214")
      (value "6.2K")
      (footprint "RES-1608")
      (description "Chip Resistor")
      (fields (field (name "PACKAGE/CASE") "R1608"))
      (libsource (lib "Miscellaneous Devices") (part "Res1"))
    )
    (comp (ref "R215")
      (value "10K")
      (footprint "RES-1608")
      (description "Chip Resistor")
      (fields (field (name "PACKAGE/CASE") "R1608"))
      (libsource (lib "Miscellaneous Devices") (part "Res1"))
    )
    (comp (ref "R216")
      (value "6.2K")
      (footprint "RES-1608")
      (description "Chip Resistor")
      (fields (field (name "PACKAGE/CASE") "R1608"))
      (libsource (lib "Miscellaneous Devices") (part "Res1"))
    )
    (comp (ref "R217")
      (value "10K")
      (footprint "RES-1608")
      (description "Chip Resistor")
      (fields (field (name "PACKAGE/CASE") "R1608"))
      (libsource (lib "Miscellaneous Devices") (part "Res1"))
    )
    (comp (ref "R218")
      (value "100K")
      (footprint "RES-1608")
      (description "Chip Resistor")
      (fields (field (name "PACKAGE/CASE") "R1608"))
      (libsource (lib "Miscellaneous Devices") (part "Res1"))
    )
    (comp (ref "R219")
      (value "0")
      (footprint "RES-1608")
      (description "Chip Resistor")
      (fields (field (name "PACKAGE/CASE") "R1608"))
      (libsource (lib "Miscellaneous Devices") (part "Res1"))
    )
    (comp (ref "R220")
      (value "2K")
      (footprint "RES-1608")
      (description "Chip Resistor")
      (fields (field (name "PACKAGE/CASE") "R1608"))
      (libsource (lib "Miscellaneous Devices") (part "Res1"))
    )
    (comp (ref "R221")
      (value "N.C")
      (footprint "RES-3216")
      (description "Chip Resistor")
      (fields (field (name "PACKAGE/CASE") "R1608"))
      (libsource (lib "Miscellaneous Devices") (part "Res1"))
    )
    (comp (ref "R222")
      (value "N.C")
      (footprint "RES-3216")
      (description "Chip Resistor")
      (fields (field (name "PACKAGE/CASE") "R1608"))
      (libsource (lib "Miscellaneous Devices") (part "Res1"))
    )
    (comp (ref "R223")
      (value "10K")
      (footprint "RES-1608")
      (description "Chip Resistor")
      (fields (field (name "PACKAGE/CASE") "R1608"))
      (libsource (lib "Miscellaneous Devices") (part "Res1"))
    )
    (comp (ref "R224")
      (value "1K")
      (footprint "RES-1608")
      (description "Chip Resistor")
      (fields (field (name "PACKAGE/CASE") "R1608"))
      (libsource (lib "Miscellaneous Devices") (part "Res1"))
    )
    (comp (ref "R225")
      (value "0")
      (footprint "RES-1608")
      (description "Chip Resistor")
      (fields (field (name "PACKAGE/CASE") "R3216"))
      (libsource (lib "Miscellaneous Devices") (part "Res1"))
    )
    (comp (ref "R226")
      (value "0")
      (footprint "RES-1608")
      (description "Chip Resistor")
      (fields (field (name "PACKAGE/CASE") "R1608"))
      (libsource (lib "Miscellaneous Devices") (part "Res1"))
    )
    (comp (ref "R227")
      (value "N.C")
      (footprint "RES-1608")
      (description "Chip Resistor")
      (fields (field (name "PACKAGE/CASE") "R2012"))
      (libsource (lib "Miscellaneous Devices") (part "Res1"))
    )
    (comp (ref "R228")
      (value "N.C")
      (footprint "RES-1608")
      (description "Chip Resistor")
      (fields (field (name "PACKAGE/CASE") "R2012"))
      (libsource (lib "Miscellaneous Devices") (part "Res1"))
    )
    (comp (ref "R229")
      (value "N.C")
      (footprint "RES-1608")
      (description "Chip Resistor")
      (fields (field (name "PACKAGE/CASE") "R2012"))
      (libsource (lib "Miscellaneous Devices") (part "Res1"))
    )
    (comp (ref "R230")
      (value "N.C")
      (footprint "RES-1608")
      (description "Chip Resistor")
      (fields (field (name "PACKAGE/CASE") "R2012"))
      (libsource (lib "Miscellaneous Devices") (part "Res1"))
    )
    (comp (ref "T2") (value "Transformer") (libsource (lib "Schematic") (part "Transformer")))
    (comp (ref "U9") (value "L6498LD") (libsource (lib "Schematic") (part "L6498LD")))
    (comp (ref "U10") (value "L6498LD") (libsource (lib "Schematic") (part "L6498LD")))
    (comp (ref "U11")
      (value "TEA2095TE/1")
      (description "LLC SR CONTROLLER IC")
      (fields (field (name "PACKAGE/CASE") "8-HSO"))
      (libsource (lib "Schematic") (part "TEA2095TE/1"))
    )
    (comp (ref "U12")
      (value "78D09AL-TN3-R")
      (description "3-TERMINALS 1A POSITIVE VOLTAGE REGULATOR")
      (fields (field (name "PACKAGE/CASE") "DPAK"))
      (libsource (lib "Schematic") (part "78D09AL-TN3-R"))
    )
    (comp (ref "U13")
      (value "EL1018(TA)-G")
      (footprint "1W-IC-CHP-4L-3_6X7_6-2_54P-L10_2-PC")
      (description "Photocoupler")
      (fields (field (name "PACKAGE/CASE") "4-SOP(2.54mm)"))
      (libsource (lib "SFH617A-2X019T") (part "SFH617A-2X019T"))
    )
    (comp (ref "U14")
      (value "L6790A")
      (description "LLC-PFC controller IC for insulated power factor corrector application")
      (fields (field (name "PACKAGE/CASE") "SO16N"))
      (libsource (lib "Schematic") (part "L6790A"))
    )
    (comp (ref "U15")
      (value "EL1018(TA)-G")
      (footprint "1W-IC-CHP-4L-3_6X7_6-2_54P-L10_2-PC")
      (description "Photocoupler")
      (fields (field (name "PACKAGE/CASE") "4-SOP(2.54mm)"))
      (libsource (lib "Schematic") (part "SFH617A-2X019T"))
    )
    (comp (ref "U16")
      (value "EL1018(TA)-G")
      (footprint "1W-IC-CHP-4L-3_6X7_6-2_54P-L10_2-PC")
      (description "Photocoupler")
      (fields (field (name "PACKAGE/CASE") "4-SOP(2.54mm)"))
      (libsource (lib "SFH617A-2X019T") (part "SFH617A-2X019T"))
    )
  )
  (nets
    (net (code "1") (name "/ACD") (class "Default")
      (node (ref "C109") (pin "1") (pinfunction "1_1") (pintype "passive"))
      (node (ref "D33") (pin "2") (pinfunction "K_2") (pintype "passive"))
      (node (ref "R172") (pin "2") (pinfunction "2_2") (pintype "passive"))
      (node (ref "R209") (pin "2") (pinfunction "2_2") (pintype "passive"))
      (node (ref "U15") (pin "3") (pinfunction "E_3") (pintype "passive"))
    )
    (net (code "2") (name "/ACD_CTRL") (class "Default")
      (node (ref "R207") (pin "2") (pinfunction "2_2") (pintype "passive"))
    )
    (net (code "3") (name "/ACL") (class "Default")
      (node (ref "BD2") (pin "3") (pinfunction "3_3") (pintype "passive"))
      (node (ref "D31") (pin "1") (pinfunction "A_1") (pintype "passive"))
    )
    (net (code "4") (name "/ACN") (class "Default")
      (node (ref "BD2") (pin "2") (pinfunction "2_2") (pintype "passive"))
      (node (ref "D32") (pin "1") (pinfunction "A_1") (pintype "passive"))
    )
    (net (code "5") (name "/BM") (class "Default")
      (node (ref "R211") (pin "1") (pinfunction "1_1") (pintype "passive"))
      (node (ref "U14") (pin "10") (pinfunction "BM_10") (pintype "passive"))
    )
    (net (code "6") (name "/CFG") (class "Default")
      (node (ref "R212") (pin "1") (pinfunction "1_1") (pintype "passive"))
      (node (ref "U14") (pin "11") (pinfunction "CFG_11") (pintype "passive"))
    )
    (net (code "7") (name "/CT") (class "Default")
      (node (ref "C110") (pin "1") (pinfunction "1_1") (pintype "passive"))
      (node (ref "U14") (pin "8") (pinfunction "CT_8") (pintype "passive"))
    )
    (net (code "8") (name "/DISCHARGE") (class "Default")
      (node (ref "Q47") (pin "3") (pinfunction "C_3") (pintype "passive"))
      (node (ref "R156") (pin "2") (pinfunction "2_2") (pintype "passive"))
      (node (ref "R179") (pin "2") (pinfunction "2_2") (pintype "passive"))
      (node (ref "R216") (pin "1") (pinfunction "1_1") (pintype "passive"))
      (node (ref "U16") (pin "2") (pinfunction "C_2") (pintype "passive"))
    )
    (net (code "9") (name "/DPC1") (class "Default")
      (node (ref "R198") (pin "2") (pinfunction "2_2") (pintype "passive"))
    )
    (net (code "10") (name "/DRV_EN") (class "Default")
      (node (ref "R224") (pin "1") (pinfunction "1_1") (pintype "passive"))
      (node (ref "U14") (pin "3") (pinfunction "DRV_EN_3") (pintype "passive"))
    )
    (net (code "11") (name "/DRV_ON") (class "Default")
      (node (ref "R217") (pin "2") (pinfunction "2_2") (pintype "passive"))
    )
    (net (code "12") (name "/DSA") (class "Default")
      (node (ref "Q25") (pin "5") (pinfunction "D_5") (pintype "passive"))
      (node (ref "Q25") (pin "6") (pinfunction "D_6") (pintype "passive"))
      (node (ref "Q25") (pin "7") (pinfunction "D_7") (pintype "passive"))
      (node (ref "Q25") (pin "8") (pinfunction "D_8") (pintype "passive"))
      (node (ref "Q26") (pin "5") (pinfunction "D_5") (pintype "passive"))
      (node (ref "Q26") (pin "6") (pinfunction "D_6") (pintype "passive"))
      (node (ref "Q26") (pin "7") (pinfunction "D_7") (pintype "passive"))
      (node (ref "Q26") (pin "8") (pinfunction "D_8") (pintype "passive"))
      (node (ref "T2") (pin "4") (pinfunction "4_4") (pintype "passive"))
      (node (ref "U11") (pin "6") (pinfunction "DSA_6") (pintype "passive"))
    )
    (net (code "13") (name "/DSB") (class "Default")
      (node (ref "Q29") (pin "5") (pinfunction "D_5") (pintype "passive"))
      (node (ref "Q29") (pin "6") (pinfunction "D_6") (pintype "passive"))
      (node (ref "Q29") (pin "7") (pinfunction "D_7") (pintype "passive"))
      (node (ref "Q29") (pin "8") (pinfunction "D_8") (pintype "passive"))
      (node (ref "Q30") (pin "5") (pinfunction "D_5") (pintype "passive"))
      (node (ref "Q30") (pin "6") (pinfunction "D_6") (pintype "passive"))
      (node (ref "Q30") (pin "7") (pinfunction "D_7") (pintype "passive"))
      (node (ref "Q30") (pin "8") (pinfunction "D_8") (pintype "passive"))
      (node (ref "T2") (pin "6") (pinfunction "6_6") (pintype "passive"))
      (node (ref "U11") (pin "3") (pinfunction "DSB_3") (pintype "passive"))
    )
    (net (code "14") (name "/FB") (class "Default")
      (node (ref "C111") (pin "1") (pinfunction "1_1") (pintype "passive"))
      (node (ref "C112") (pin "1") (pinfunction "1_1") (pintype "passive"))
      (node (ref "U13") (pin "4") (pinfunction "C_4") (pintype "passive"))
      (node (ref "U14") (pin "9") (pinfunction "FB_9") (pintype "passive"))
    )
    (net (code "15") (name "/GDA") (class "Default")
      (node (ref "Q25") (pin "4") (pinfunction "G_4") (pintype "passive"))
      (node (ref "Q26") (pin "4") (pinfunction "G_4") (pintype "passive"))
      (node (ref "R116") (pin "1") (pinfunction "1_1") (pintype "passive"))
      (node (ref "R117") (pin "1") (pinfunction "1_1") (pintype "passive"))
      (node (ref "R164") (pin "1") (pinfunction "1_1") (pintype "passive"))
    )
    (net (code "16") (name "/GDB") (class "Default")
      (node (ref "Q29") (pin "4") (pinfunction "G_4") (pintype "passive"))
      (node (ref "Q30") (pin "4") (pinfunction "G_4") (pintype "passive"))
      (node (ref "R134") (pin "1") (pinfunction "1_1") (pintype "passive"))
      (node (ref "R135") (pin "1") (pinfunction "1_1") (pintype "passive"))
      (node (ref "R163") (pin "2") (pinfunction "2_2") (pintype "passive"))
    )
    (net (code "17") (name "/HOUT1") (class "Default")
      (node (ref "R118") (pin "1") (pinfunction "1_1") (pintype "passive"))
      (node (ref "U14") (pin "16") (pinfunction "HOUT1_16") (pintype "passive"))
    )
    (net (code "18") (name "/HOUT2") (class "Default")
      (node (ref "R160") (pin "1") (pinfunction "1_1") (pintype "passive"))
      (node (ref "U14") (pin "14") (pinfunction "HOUT2_14") (pintype "passive"))
    )
    (net (code "19") (name "/LOUT1") (class "Default")
      (node (ref "R119") (pin "1") (pinfunction "1_1") (pintype "passive"))
      (node (ref "U14") (pin "15") (pinfunction "LOUT1_15") (pintype "passive"))
    )
    (net (code "20") (name "/LOUT2") (class "Default")
      (node (ref "R161") (pin "1") (pinfunction "1_1") (pintype "passive"))
      (node (ref "U14") (pin "13") (pinfunction "LOUT2_13") (pintype "passive"))
    )
    (net (code "21") (name "/OUTH_1") (class "Default")
      (node (ref "D17") (pin "2") (pinfunction "K_2") (pintype "passive"))
      (node (ref "R115") (pin "2") (pinfunction "2_2") (pintype "passive"))
      (node (ref "U9") (pin "12") (pinfunction "HVG_12") (pintype "passive"))
    )
    (net (code "22") (name "/OUTH_2") (class "Default")
      (node (ref "D22") (pin "2") (pinfunction "K_2") (pintype "passive"))
      (node (ref "R159") (pin "2") (pinfunction "2_2") (pintype "passive"))
      (node (ref "U10") (pin "12") (pinfunction "HVG_12") (pintype "passive"))
    )
    (net (code "23") (name "/OUTL_1") (class "Default")
      (node (ref "D19") (pin "2") (pinfunction "K_2") (pintype "passive"))
      (node (ref "R121") (pin "2") (pinfunction "2_2") (pintype "passive"))
      (node (ref "U9") (pin "6") (pinfunction "LVG_6") (pintype "passive"))
    )
    (net (code "24") (name "/OUTL_2") (class "Default")
      (node (ref "D24") (pin "2") (pinfunction "K_2") (pintype "passive"))
      (node (ref "R165") (pin "2") (pinfunction "2_2") (pintype "passive"))
      (node (ref "U10") (pin "6") (pinfunction "LVG_6") (pintype "passive"))
    )
    (net (code "25") (name "/OUTb_1") (class "Default")
      (node (ref "C63") (pin "2") (pinfunction "2_2") (pintype "passive"))
      (node (ref "C64") (pin "2") (pinfunction "2_2") (pintype "passive"))
      (node (ref "Q27") (pin "2") (pinfunction "DS_2") (pintype "passive"))
      (node (ref "R227") (pin "1") (pinfunction "1_1") (pintype "passive"))
      (node (ref "U9") (pin "11") (pinfunction "OUT_11") (pintype "passive"))
    )
    (net (code "26") (name "/OUTb_2") (class "Default")
      (node (ref "C72") (pin "2") (pinfunction "2_2") (pintype "passive"))
      (node (ref "C74") (pin "2") (pinfunction "2_2") (pintype "passive"))
      (node (ref "Q32") (pin "2") (pinfunction "DS_2") (pintype "passive"))
      (node (ref "R229") (pin "1") (pinfunction "1_1") (pintype "passive"))
      (node (ref "U10") (pin "11") (pinfunction "OUT_11") (pintype "passive"))
    )
    (net (code "27") (name "/PGND_1") (class "Default")
      (node (ref "C65") (pin "2") (pinfunction "2_2") (pintype "passive"))
      (node (ref "C67") (pin "2") (pinfunction "2_2") (pintype "passive"))
      (node (ref "Q28") (pin "2") (pinfunction "DS_2") (pintype "passive"))
      (node (ref "R228") (pin "1") (pinfunction "1_1") (pintype "passive"))
      (node (ref "U9") (pin "5") (pinfunction "PGND_5") (pintype "passive"))
    )
    (net (code "28") (name "/PGND_2") (class "Default")
      (node (ref "C78") (pin "2") (pinfunction "2_2") (pintype "passive"))
      (node (ref "C79") (pin "2") (pinfunction "2_2") (pintype "passive"))
      (node (ref "Q34") (pin "2") (pinfunction "DS_2") (pintype "passive"))
      (node (ref "R230") (pin "1") (pinfunction "1_1") (pintype "passive"))
      (node (ref "U10") (pin "5") (pinfunction "PGND_5") (pintype "passive"))
    )
    (net (code "29") (name "/RT") (class "Default")
      (node (ref "R184") (pin "2") (pinfunction "2_2") (pintype "passive"))
      (node (ref "R210") (pin "1") (pinfunction "1_1") (pintype "passive"))
      (node (ref "U14") (pin "7") (pinfunction "RT_7") (pintype "passive"))
    )
    (net (code "30") (name "/ZCD") (class "Default")
      (node (ref "R206") (pin "2") (pinfunction "2_2") (pintype "passive"))
      (node (ref "R208") (pin "1") (pinfunction "1_1") (pintype "passive"))
      (node (ref "U14") (pin "12") (pinfunction "ZCD_12") (pintype "passive"))
    )
    (net (code "31") (name "/ZCD_AUX") (class "Default")
      (node (ref "R206") (pin "1") (pinfunction "1_1") (pintype "passive"))
      (node (ref "T2") (pin "7") (pinfunction "7_7") (pintype "passive"))
    )
    (net (code "32") (name "12VM") (class "Default")
      (node (ref "R205") (pin "2") (pinfunction "2_2") (pintype "passive"))
      (node (ref "R214") (pin "2") (pinfunction "2_2") (pintype "passive"))
      (node (ref "R216") (pin "2") (pinfunction "2_2") (pintype "passive"))
    )
    (net (code "33") (name "12VT") (class "Default")
      (node (ref "Q33") (pin "2") (pinfunction "E_2") (pintype "passive"))
      (node (ref "R167") (pin "1") (pinfunction "1_1") (pintype "passive"))
      (node (ref "R168") (pin "1") (pinfunction "1_1") (pintype "passive"))
      (node (ref "R170") (pin "1") (pinfunction "1_1") (pintype "passive"))
      (node (ref "R222") (pin "2") (pinfunction "2_2") (pintype "passive"))
    )
    (net (code "34") (name "12V_FB") (class "Default")
      (node (ref "Q40") (pin "2") (pinfunction "SOURCE_2") (pintype "passive"))
      (node (ref "R178") (pin "2") (pinfunction "2_2") (pintype "passive"))
      (node (ref "R197") (pin "1") (pinfunction "1_1") (pintype "passive"))
      (node (ref "R200") (pin "2") (pinfunction "2_2") (pintype "passive"))
    )
    (net (code "35") (name "25VD") (class "Default")
      (node (ref "C100") (pin "1") (pinfunction "1_1") (pintype "passive"))
      (node (ref "C66") (pin "1") (pinfunction "1_1") (pintype "passive"))
      (node (ref "L2") (pin "2") (pinfunction "2_2") (pintype "passive"))
      (node (ref "Q40") (pin "3") (pinfunction "DRAIN_3") (pintype "passive"))
      (node (ref "R180") (pin "2") (pinfunction "2_2") (pintype "passive"))
      (node (ref "R181") (pin "1") (pinfunction "1_1") (pintype "passive"))
      (node (ref "R219") (pin "2") (pinfunction "2_2") (pintype "passive"))
      (node (ref "R221") (pin "2") (pinfunction "2_2") (pintype "passive"))
    )
    (net (code "36") (name "BOOT1") (class "Default")
      (node (ref "C63") (pin "1") (pinfunction "1_1") (pintype "passive"))
      (node (ref "R113") (pin "2") (pinfunction "2_2") (pintype "passive"))
      (node (ref "U9") (pin "13") (pinfunction "BOOT_13") (pintype "passive"))
    )
    (net (code "37") (name "BOOT2") (class "Default")
      (node (ref "C72") (pin "1") (pinfunction "1_1") (pintype "passive"))
      (node (ref "R155") (pin "2") (pinfunction "2_2") (pintype "passive"))
      (node (ref "U10") (pin "13") (pinfunction "BOOT_13") (pintype "passive"))
    )
    (net (code "38") (name "Net-(C75-Pad1)") (class "Default")
      (node (ref "C75") (pin "1") (pinfunction "1_1") (pintype "passive"))
      (node (ref "C76") (pin "1") (pinfunction "1_1") (pintype "passive"))
      (node (ref "C77") (pin "1") (pinfunction "1_1") (pintype "passive"))
      (node (ref "T2") (pin "10") (pinfunction "10_10") (pintype "passive"))
    )
    (net (code "39") (name "Net-(C93-Pad1)") (class "Default")
      (node (ref "C93") (pin "1") (pinfunction "1_1") (pintype "passive"))
      (node (ref "R180") (pin "1") (pinfunction "1_1") (pintype "passive"))
    )
    (net (code "40") (name "Net-(C93-Pad2)") (class "Default")
      (node (ref "C93") (pin "2") (pinfunction "2_2") (pintype "passive"))
      (node (ref "C94") (pin "1") (pinfunction "1_1") (pintype "passive"))
    )
    (net (code "41") (name "Net-(C98-Pad2)") (class "Default")
      (node (ref "C98") (pin "2") (pinfunction "2_2") (pintype "passive"))
      (node (ref "C99") (pin "2") (pinfunction "2_2") (pintype "passive"))
      (node (ref "R187") (pin "2") (pinfunction "2_2") (pintype "passive"))
    )
    (net (code "42") (name "Net-(C105-Pad1)") (class "Default")
      (node (ref "C105") (pin "1") (pinfunction "1_1") (pintype "passive"))
      (node (ref "R188") (pin "1") (pinfunction "1_1") (pintype "passive"))
      (node (ref "R193") (pin "1") (pinfunction "1_1") (pintype "passive"))
    )
    (net (code "43") (name "Net-(D16-K)") (class "Default")
      (node (ref "D16") (pin "2") (pinfunction "K_2") (pintype "passive"))
      (node (ref "R113") (pin "1") (pinfunction "1_1") (pintype "passive"))
    )
    (net (code "44") (name "Net-(D17-A)") (class "Default")
      (node (ref "D17") (pin "1") (pinfunction "A_1") (pintype "passive"))
      (node (ref "R114") (pin "2") (pinfunction "2_2") (pintype "passive"))
    )
    (net (code "45") (name "Net-(D19-A)") (class "Default")
      (node (ref "D19") (pin "1") (pinfunction "A_1") (pintype "passive"))
      (node (ref "R120") (pin "2") (pinfunction "2_2") (pintype "passive"))
    )
    (net (code "46") (name "Net-(D21-K)") (class "Default")
      (node (ref "D21") (pin "2") (pinfunction "K_2") (pintype "passive"))
      (node (ref "R155") (pin "1") (pinfunction "1_1") (pintype "passive"))
    )
    (net (code "47") (name "Net-(D22-A)") (class "Default")
      (node (ref "D22") (pin "1") (pinfunction "A_1") (pintype "passive"))
      (node (ref "R157") (pin "2") (pinfunction "2_2") (pintype "passive"))
    )
    (net (code "48") (name "Net-(D24-A)") (class "Default")
      (node (ref "D24") (pin "1") (pinfunction "A_1") (pintype "passive"))
      (node (ref "R162") (pin "2") (pinfunction "2_2") (pintype "passive"))
    )
    (net (code "49") (name "Net-(D26-K)") (class "Default")
      (node (ref "C86") (pin "1") (pinfunction "1_1") (pintype "passive"))
      (node (ref "C87") (pin "1") (pinfunction "1_1") (pintype "passive"))
      (node (ref "C88") (pin "1") (pinfunction "1_1") (pintype "passive"))
      (node (ref "D26") (pin "2") (pinfunction "K_2") (pintype "passive"))
      (node (ref "R166") (pin "2") (pinfunction "2_2") (pintype "passive"))
      (node (ref "U11") (pin "7") (pinfunction "VCC_7") (pintype "passive"))
    )
    (net (code "50") (name "Net-(D27-A)") (class "Default")
      (node (ref "D27") (pin "1") (pinfunction "A_1") (pintype "passive"))
      (node (ref "D28") (pin "2") (pinfunction "K_2") (pintype "passive"))
    )
    (net (code "51") (name "Net-(D31-K)") (class "Default")
      (node (ref "D31") (pin "2") (pinfunction "K_2") (pintype "passive"))
      (node (ref "D32") (pin "2") (pinfunction "K_2") (pintype "passive"))
      (node (ref "R196") (pin "1") (pinfunction "1_1") (pintype "passive"))
      (node (ref "R225") (pin "2") (pinfunction "2_2") (pintype "passive"))
    )
    (net (code "52") (name "Net-(D34-A)") (class "Default")
      (node (ref "C114") (pin "2") (pinfunction "2_2") (pintype "passive"))
      (node (ref "D34") (pin "1") (pinfunction "A_1") (pintype "passive"))
      (node (ref "Q48") (pin "1") (pinfunction "G_1") (pintype "passive"))
      (node (ref "R220") (pin "2") (pinfunction "2_2") (pintype "passive"))
    )
    (net (code "53") (name "Net-(D34-K)") (class "Default")
      (node (ref "D34") (pin "2") (pinfunction "K_2") (pintype "passive"))
      (node (ref "R219") (pin "1") (pinfunction "1_1") (pintype "passive"))
    )
    (net (code "54") (name "Net-(L2-Pad1)") (class "Default")
      (node (ref "L2") (pin "1") (pinfunction "1_1") (pintype "passive"))
      (node (ref "R122") (pin "2") (pinfunction "2_2") (pintype "passive"))
      (node (ref "R123") (pin "2") (pinfunction "2_2") (pintype "passive"))
      (node (ref "R124") (pin "2") (pinfunction "2_2") (pintype "passive"))
      (node (ref "R125") (pin "2") (pinfunction "2_2") (pintype "passive"))
      (node (ref "R126") (pin "2") (pinfunction "2_2") (pintype "passive"))
      (node (ref "R127") (pin "2") (pinfunction "2_2") (pintype "passive"))
      (node (ref "R128") (pin "2") (pinfunction "2_2") (pintype "passive"))
      (node (ref "R129") (pin "2") (pinfunction "2_2") (pintype "passive"))
      (node (ref "R130") (pin "2") (pinfunction "2_2") (pintype "passive"))
      (node (ref "R131") (pin "2") (pinfunction "2_2") (pintype "passive"))
      (node (ref "R132") (pin "2") (pinfunction "2_2") (pintype "passive"))
      (node (ref "R133") (pin "2") (pinfunction "2_2") (pintype "passive"))
      (node (ref "R137") (pin "2") (pinfunction "2_2") (pintype "passive"))
      (node (ref "R138") (pin "2") (pinfunction "2_2") (pintype "passive"))
      (node (ref "R139") (pin "2") (pinfunction "2_2") (pintype "passive"))
      (node (ref "R140") (pin "2") (pinfunction "2_2") (pintype "passive"))
      (node (ref "R141") (pin "2") (pinfunction "2_2") (pintype "passive"))
      (node (ref "R142") (pin "2") (pinfunction "2_2") (pintype "passive"))
      (node (ref "R143") (pin "2") (pinfunction "2_2") (pintype "passive"))
      (node (ref "R144") (pin "2") (pinfunction "2_2") (pintype "passive"))
      (node (ref "R145") (pin "2") (pinfunction "2_2") (pintype "passive"))
      (node (ref "R146") (pin "2") (pinfunction "2_2") (pintype "passive"))
      (node (ref "R147") (pin "2") (pinfunction "2_2") (pintype "passive"))
      (node (ref "R148") (pin "2") (pinfunction "2_2") (pintype "passive"))
      (node (ref "R149") (pin "2") (pinfunction "2_2") (pintype "passive"))
      (node (ref "R150") (pin "2") (pinfunction "2_2") (pintype "passive"))
      (node (ref "R151") (pin "2") (pinfunction "2_2") (pintype "passive"))
      (node (ref "R152") (pin "2") (pinfunction "2_2") (pintype "passive"))
      (node (ref "R153") (pin "2") (pinfunction "2_2") (pintype "passive"))
      (node (ref "R154") (pin "2") (pinfunction "2_2") (pintype "passive"))
      (node (ref "T2") (pin "5") (pinfunction "5_5") (pintype "passive"))
    )
    (net (code "55") (name "Net-(Q27-G)") (class "Default")
      (node (ref "C64") (pin "1") (pinfunction "1_1") (pintype "passive"))
      (node (ref "Q27") (pin "1") (pinfunction "G_1") (pintype "passive"))
      (node (ref "R114") (pin "1") (pinfunction "1_1") (pintype "passive"))
      (node (ref "R115") (pin "1") (pinfunction "1_1") (pintype "passive"))
    )
    (net (code "56") (name "Net-(Q28-D)") (class "Default")
      (node (ref "Q27") (pin "3") (pinfunction "PS_3") (pintype "passive"))
      (node (ref "Q27") (pin "4") (pinfunction "PS_4") (pintype "passive"))
      (node (ref "Q27") (pin "5") (pinfunction "PS_5") (pintype "passive"))
      (node (ref "Q27") (pin "6") (pinfunction "PS_6") (pintype "passive"))
      (node (ref "Q27") (pin "7") (pinfunction "PS_7") (pintype "passive"))
      (node (ref "Q27") (pin "8") (pinfunction "PS_8") (pintype "passive"))
      (node (ref "Q28") (pin "TAP") (pinfunction "D_TAP") (pintype "passive"))
      (node (ref "R227") (pin "2") (pinfunction "2_2") (pintype "passive"))
      (node (ref "T2") (pin "12") (pinfunction "12_12") (pintype "passive"))
    )
    (net (code "57") (name "Net-(Q28-G)") (class "Default")
      (node (ref "C67") (pin "1") (pinfunction "1_1") (pintype "passive"))
      (node (ref "Q28") (pin "1") (pinfunction "G_1") (pintype "passive"))
      (node (ref "R120") (pin "1") (pinfunction "1_1") (pintype "passive"))
      (node (ref "R121") (pin "1") (pinfunction "1_1") (pintype "passive"))
    )
    (net (code "58") (name "Net-(Q31-D)") (class "Default")
      (node (ref "Q31") (pin "3") (pinfunction "D_3") (pintype "passive"))
      (node (ref "R137") (pin "1") (pinfunction "1_1") (pintype "passive"))
      (node (ref "R138") (pin "1") (pinfunction "1_1") (pintype "passive"))
      (node (ref "R139") (pin "1") (pinfunction "1_1") (pintype "passive"))
      (node (ref "R140") (pin "1") (pinfunction "1_1") (pintype "passive"))
      (node (ref "R141") (pin "1") (pinfunction "1_1") (pintype "passive"))
      (node (ref "R142") (pin "1") (pinfunction "1_1") (pintype "passive"))
      (node (ref "R143") (pin "1") (pinfunction "1_1") (pintype "passive"))
      (node (ref "R144") (pin "1") (pinfunction "1_1") (pintype "passive"))
      (node (ref "R145") (pin "1") (pinfunction "1_1") (pintype "passive"))
      (node (ref "R146") (pin "1") (pinfunction "1_1") (pintype "passive"))
      (node (ref "R147") (pin "1") (pinfunction "1_1") (pintype "passive"))
      (node (ref "R148") (pin "1") (pinfunction "1_1") (pintype "passive"))
      (node (ref "R149") (pin "1") (pinfunction "1_1") (pintype "passive"))
      (node (ref "R150") (pin "1") (pinfunction "1_1") (pintype "passive"))
      (node (ref "R151") (pin "1") (pinfunction "1_1") (pintype "passive"))
      (node (ref "R152") (pin "1") (pinfunction "1_1") (pintype "passive"))
      (node (ref "R153") (pin "1") (pinfunction "1_1") (pintype "passive"))
      (node (ref "R154") (pin "1") (pinfunction "1_1") (pintype "passive"))
    )
    (net (code "59") (name "Net-(Q31-G)") (class "Default")
      (node (ref "C73") (pin "1") (pinfunction "1_1") (pintype "passive"))
      (node (ref "Q31") (pin "1") (pinfunction "G_1") (pintype "passive"))
      (node (ref "R156") (pin "1") (pinfunction "1_1") (pintype "passive"))
      (node (ref "R158") (pin "1") (pinfunction "1_1") (pintype "passive"))
    )
    (net (code "60") (name "Net-(Q32-G)") (class "Default")
      (node (ref "C74") (pin "1") (pinfunction "1_1") (pintype "passive"))
      (node (ref "Q32") (pin "1") (pinfunction "G_1") (pintype "passive"))
      (node (ref "R157") (pin "1") (pinfunction "1_1") (pintype "passive"))
      (node (ref "R159") (pin "1") (pinfunction "1_1") (pintype "passive"))
    )
    (net (code "61") (name "Net-(Q33-B)") (class "Default")
      (node (ref "Q33") (pin "1") (pinfunction "B_1") (pintype "passive"))
      (node (ref "R168") (pin "2") (pinfunction "2_2") (pintype "passive"))
      (node (ref "R171") (pin "1") (pinfunction "1_1") (pintype "passive"))
    )
    (net (code "62") (name "Net-(Q33-C)") (class "Default")
      (node (ref "C83") (pin "1") (pinfunction "1_1") (pintype "passive"))
      (node (ref "Q33") (pin "3") (pinfunction "C_3") (pintype "passive"))
      (node (ref "U12") (pin "1") (pinfunction "IN_1") (pintype "passive"))
    )
    (net (code "63") (name "Net-(Q34-D)") (class "Default")
      (node (ref "C75") (pin "2") (pinfunction "2_2") (pintype "passive"))
      (node (ref "C76") (pin "2") (pinfunction "2_2") (pintype "passive"))
      (node (ref "C77") (pin "2") (pinfunction "2_2") (pintype "passive"))
      (node (ref "Q32") (pin "3") (pinfunction "PS_3") (pintype "passive"))
      (node (ref "Q32") (pin "4") (pinfunction "PS_4") (pintype "passive"))
      (node (ref "Q32") (pin "5") (pinfunction "PS_5") (pintype "passive"))
      (node (ref "Q32") (pin "6") (pinfunction "PS_6") (pintype "passive"))
      (node (ref "Q32") (pin "7") (pinfunction "PS_7") (pintype "passive"))
      (node (ref "Q32") (pin "8") (pinfunction "PS_8") (pintype "passive"))
      (node (ref "Q34") (pin "TAP") (pinfunction "D_TAP") (pintype "passive"))
      (node (ref "R229") (pin "2") (pinfunction "2_2") (pintype "passive"))
    )
    (net (code "64") (name "Net-(Q34-G)") (class "Default")
      (node (ref "C79") (pin "1") (pinfunction "1_1") (pintype "passive"))
      (node (ref "Q34") (pin "1") (pinfunction "G_1") (pintype "passive"))
      (node (ref "R162") (pin "1") (pinfunction "1_1") (pintype "passive"))
      (node (ref "R165") (pin "1") (pinfunction "1_1") (pintype "passive"))
    )
    (net (code "65") (name "Net-(Q35-D)") (class "Default")
      (node (ref "C90") (pin "1") (pinfunction "1_1") (pintype "passive"))
      (node (ref "C91") (pin "1") (pinfunction "1_1") (pintype "passive"))
      (node (ref "Q35") (pin "3") (pinfunction "D_3") (pintype "passive"))
      (node (ref "Q37") (pin "1") (pinfunction "B_1") (pintype "passive"))
      (node (ref "Q38") (pin "3") (pinfunction "D_3") (pintype "passive"))
      (node (ref "R170") (pin "2") (pinfunction "2_2") (pintype "passive"))
    )
    (net (code "66") (name "Net-(Q35-G)") (class "Default")
      (node (ref "C84") (pin "1") (pinfunction "1_1") (pintype "passive"))
      (node (ref "Q35") (pin "1") (pinfunction "G_1") (pintype "passive"))
      (node (ref "Q36") (pin "3") (pinfunction "D_3") (pintype "passive"))
      (node (ref "R167") (pin "2") (pinfunction "2_2") (pintype "passive"))
    )
    (net (code "67") (name "Net-(Q36-G)") (class "Default")
      (node (ref "C85") (pin "1") (pinfunction "1_1") (pintype "passive"))
      (node (ref "Q36") (pin "1") (pinfunction "G_1") (pintype "passive"))
      (node (ref "R172") (pin "1") (pinfunction "1_1") (pintype "passive"))
      (node (ref "R174") (pin "1") (pinfunction "1_1") (pintype "passive"))
    )
    (net (code "68") (name "Net-(Q37-C)") (class "Default")
      (node (ref "Q37") (pin "3") (pinfunction "C_3") (pintype "passive"))
      (node (ref "R171") (pin "2") (pinfunction "2_2") (pintype "passive"))
    )
    (net (code "69") (name "Net-(Q38-G)") (class "Default")
      (node (ref "C92") (pin "1") (pinfunction "1_1") (pintype "passive"))
      (node (ref "Q38") (pin "1") (pinfunction "G_1") (pintype "passive"))
      (node (ref "R179") (pin "1") (pinfunction "1_1") (pintype "passive"))
      (node (ref "R182") (pin "1") (pinfunction "1_1") (pintype "passive"))
    )
    (net (code "70") (name "Net-(Q39-B)") (class "Default")
      (node (ref "Q39") (pin "1") (pinfunction "B_1") (pintype "passive"))
      (node (ref "R186") (pin "2") (pinfunction "2_2") (pintype "passive"))
      (node (ref "R223") (pin "1") (pinfunction "1_1") (pintype "passive"))
    )
    (net (code "71") (name "Net-(Q40-GATE)") (class "Default")
      (node (ref "Q40") (pin "1") (pinfunction "GATE_1") (pintype "passive"))
      (node (ref "R195") (pin "1") (pinfunction "1_1") (pintype "passive"))
    )
    (net (code "72") (name "Net-(Q41-D)") (class "Default")
      (node (ref "Q41") (pin "3") (pinfunction "D_3") (pintype "passive"))
      (node (ref "R223") (pin "2") (pinfunction "2_2") (pintype "passive"))
    )
    (net (code "73") (name "Net-(Q41-G)") (class "Default")
      (node (ref "C104") (pin "1") (pinfunction "1_1") (pintype "passive"))
      (node (ref "Q41") (pin "1") (pinfunction "G_1") (pintype "passive"))
      (node (ref "R201") (pin "1") (pinfunction "1_1") (pintype "passive"))
      (node (ref "R224") (pin "2") (pinfunction "2_2") (pintype "passive"))
    )
    (net (code "74") (name "Net-(Q42-D)") (class "Default")
      (node (ref "Q42") (pin "3") (pinfunction "D_3") (pintype "passive"))
      (node (ref "R193") (pin "2") (pinfunction "2_2") (pintype "passive"))
    )
    (net (code "75") (name "Net-(Q42-G)") (class "Default")
      (node (ref "C106") (pin "1") (pinfunction "1_1") (pintype "passive"))
      (node (ref "Q42") (pin "1") (pinfunction "G_1") (pintype "passive"))
      (node (ref "R198") (pin "1") (pinfunction "1_1") (pintype "passive"))
      (node (ref "R202") (pin "2") (pinfunction "2_2") (pintype "passive"))
    )
    (net (code "76") (name "Net-(Q43-D)") (class "Default")
      (node (ref "Q43") (pin "3") (pinfunction "D_3") (pintype "passive"))
      (node (ref "R184") (pin "1") (pinfunction "1_1") (pintype "passive"))
    )
    (net (code "77") (name "Net-(Q43-G)") (class "Default")
      (node (ref "C101") (pin "1") (pinfunction "1_1") (pintype "passive"))
      (node (ref "Q43") (pin "1") (pinfunction "G_1") (pintype "passive"))
      (node (ref "Q45") (pin "3") (pinfunction "D_3") (pintype "passive"))
      (node (ref "R194") (pin "2") (pinfunction "2_2") (pintype "passive"))
      (node (ref "R203") (pin "1") (pinfunction "1_1") (pintype "passive"))
    )
    (net (code "78") (name "Net-(Q44-K)") (class "Default")
      (node (ref "C95") (pin "2") (pinfunction "2_2") (pintype "passive"))
      (node (ref "Q44") (pin "2") (pinfunction "K_2") (pintype "passive"))
      (node (ref "R183") (pin "2") (pinfunction "2_2") (pintype "passive"))
      (node (ref "R187") (pin "1") (pinfunction "1_1") (pintype "passive"))
      (node (ref "U13") (pin "2") (pinfunction "C_2") (pintype "passive"))
    )
    (net (code "79") (name "Net-(Q44-R)") (class "Default")
      (node (ref "C94") (pin "2") (pinfunction "2_2") (pintype "passive"))
      (node (ref "C95") (pin "1") (pinfunction "1_1") (pintype "passive"))
      (node (ref "C98") (pin "1") (pinfunction "1_1") (pintype "passive"))
      (node (ref "C99") (pin "1") (pinfunction "1_1") (pintype "passive"))
      (node (ref "Q44") (pin "1") (pinfunction "R_1") (pintype "passive"))
      (node (ref "R185") (pin "2") (pinfunction "2_2") (pintype "passive"))
      (node (ref "R188") (pin "2") (pinfunction "2_2") (pintype "passive"))
      (node (ref "R192") (pin "1") (pinfunction "1_1") (pintype "passive"))
    )
    (net (code "80") (name "Net-(Q45-G)") (class "Default")
      (node (ref "C102") (pin "1") (pinfunction "1_1") (pintype "passive"))
      (node (ref "Q45") (pin "1") (pinfunction "G_1") (pintype "passive"))
      (node (ref "R190") (pin "2") (pinfunction "2_2") (pintype "passive"))
      (node (ref "R191") (pin "1") (pinfunction "1_1") (pintype "passive"))
    )
    (net (code "81") (name "Net-(Q46-K)") (class "Default")
      (node (ref "C107") (pin "2") (pinfunction "2_2") (pintype "passive"))
      (node (ref "Q46") (pin "2") (pinfunction "K_2") (pintype "passive"))
      (node (ref "R195") (pin "2") (pinfunction "2_2") (pintype "passive"))
      (node (ref "R200") (pin "1") (pinfunction "1_1") (pintype "passive"))
    )
    (net (code "82") (name "Net-(Q46-R)") (class "Default")
      (node (ref "C107") (pin "1") (pinfunction "1_1") (pintype "passive"))
      (node (ref "Q46") (pin "1") (pinfunction "R_1") (pintype "passive"))
      (node (ref "R197") (pin "2") (pinfunction "2_2") (pintype "passive"))
      (node (ref "R204") (pin "1") (pinfunction "1_1") (pintype "passive"))
    )
    (net (code "83") (name "Net-(Q47-B)") (class "Default")
      (node (ref "C113") (pin "2") (pinfunction "2_2") (pintype "passive"))
      (node (ref "Q47") (pin "1") (pinfunction "B_1") (pintype "passive"))
      (node (ref "Q48") (pin "3") (pinfunction "D_3") (pintype "passive"))
      (node (ref "R217") (pin "1") (pinfunction "1_1") (pintype "passive"))
      (node (ref "R218") (pin "2") (pinfunction "2_2") (pintype "passive"))
    )
    (net (code "84") (name "Net-(R136-Pad1)") (class "Default")
      (node (ref "R136") (pin "1") (pinfunction "1_1") (pintype "passive"))
      (node (ref "T2") (pin "8") (pinfunction "8_8") (pintype "passive"))
    )
    (net (code "85") (name "Net-(R181-Pad2)") (class "Default")
      (node (ref "R181") (pin "2") (pinfunction "2_2") (pintype "passive"))
      (node (ref "R185") (pin "1") (pinfunction "1_1") (pintype "passive"))
    )
    (net (code "86") (name "Net-(R189-Pad1)") (class "Default")
      (node (ref "R189") (pin "1") (pinfunction "1_1") (pintype "passive"))
      (node (ref "R196") (pin "2") (pinfunction "2_2") (pintype "passive"))
    )
    (net (code "87") (name "Net-(R192-Pad2)") (class "Default")
      (node (ref "R192") (pin "2") (pinfunction "2_2") (pintype "passive"))
      (node (ref "R199") (pin "1") (pinfunction "1_1") (pintype "passive"))
    )
    (net (code "88") (name "Net-(R208-Pad2)") (class "Default")
      (node (ref "R208") (pin "2") (pinfunction "2_2") (pintype "passive"))
      (node (ref "R213") (pin "1") (pinfunction "1_1") (pintype "passive"))
    )
    (net (code "89") (name "Net-(R210-Pad2)") (class "Default")
      (node (ref "R210") (pin "2") (pinfunction "2_2") (pintype "passive"))
      (node (ref "R215") (pin "1") (pinfunction "1_1") (pintype "passive"))
    )
    (net (code "90") (name "Net-(U9-HIN)") (class "Default")
      (node (ref "C69") (pin "1") (pinfunction "1_1") (pintype "passive"))
      (node (ref "R118") (pin "2") (pinfunction "2_2") (pintype "passive"))
      (node (ref "U9") (pin "1") (pinfunction "HIN_1") (pintype "passive"))
    )
    (net (code "91") (name "Net-(U9-LIN)") (class "Default")
      (node (ref "C70") (pin "1") (pinfunction "1_1") (pintype "passive"))
      (node (ref "R119") (pin "2") (pinfunction "2_2") (pintype "passive"))
      (node (ref "U9") (pin "2") (pinfunction "LIN_2") (pintype "passive"))
    )
    (net (code "92") (name "Net-(U10-HIN)") (class "Default")
      (node (ref "C81") (pin "1") (pinfunction "1_1") (pintype "passive"))
      (node (ref "R160") (pin "2") (pinfunction "2_2") (pintype "passive"))
      (node (ref "U10") (pin "1") (pinfunction "HIN_1") (pintype "passive"))
    )
    (net (code "93") (name "Net-(U10-LIN)") (class "Default")
      (node (ref "C82") (pin "1") (pinfunction "1_1") (pintype "passive"))
      (node (ref "R161") (pin "2") (pinfunction "2_2") (pintype "passive"))
      (node (ref "U10") (pin "2") (pinfunction "LIN_2") (pintype "passive"))
    )
    (net (code "94") (name "Net-(U11-GDA)") (class "Default")
      (node (ref "R164") (pin "2") (pinfunction "2_2") (pintype "passive"))
      (node (ref "U11") (pin "8") (pinfunction "GDA_8") (pintype "passive"))
    )
    (net (code "95") (name "Net-(U11-GDB)") (class "Default")
      (node (ref "R163") (pin "1") (pinfunction "1_1") (pintype "passive"))
      (node (ref "U11") (pin "1") (pinfunction "GDB_1") (pintype "passive"))
    )
    (net (code "96") (name "Net-(U12-OUT)") (class "Default")
      (node (ref "C89") (pin "1") (pinfunction "1_1") (pintype "passive"))
      (node (ref "R166") (pin "1") (pinfunction "1_1") (pintype "passive"))
      (node (ref "U12") (pin "3") (pinfunction "OUT_3") (pintype "passive"))
    )
    (net (code "97") (name "Net-(U13A-A)") (class "Default")
      (node (ref "R178") (pin "1") (pinfunction "1_1") (pintype "passive"))
      (node (ref "R183") (pin "1") (pinfunction "1_1") (pintype "passive"))
      (node (ref "R221") (pin "1") (pinfunction "1_1") (pintype "passive"))
      (node (ref "R222") (pin "1") (pinfunction "1_1") (pintype "passive"))
      (node (ref "U13") (pin "1") (pinfunction "A_1") (pintype "passive"))
    )
    (net (code "98") (name "Net-(U14-HVSU)") (class "Default")
      (node (ref "R225") (pin "1") (pinfunction "1_1") (pintype "passive"))
      (node (ref "U14") (pin "1") (pinfunction "HVSU_1") (pintype "passive"))
    )
    (net (code "99") (name "Net-(U14-ISEN)") (class "Default")
      (node (ref "R226") (pin "2") (pinfunction "2_2") (pintype "passive"))
      (node (ref "U14") (pin "6") (pinfunction "ISEN_6") (pintype "passive"))
    )
    (net (code "100") (name "Net-(U15A-A)") (class "Default")
      (node (ref "R207") (pin "1") (pinfunction "1_1") (pintype "passive"))
      (node (ref "U15") (pin "1") (pinfunction "A_1") (pintype "passive"))
    )
    (net (code "101") (name "Net-(U15B-C)") (class "Default")
      (node (ref "R205") (pin "1") (pinfunction "1_1") (pintype "passive"))
      (node (ref "U15") (pin "4") (pinfunction "C_4") (pintype "passive"))
    )
    (net (code "102") (name "Net-(U16A-A)") (class "Default")
      (node (ref "R214") (pin "1") (pinfunction "1_1") (pintype "passive"))
      (node (ref "U16") (pin "1") (pinfunction "A_1") (pintype "passive"))
    )
    (net (code "103") (name "Net-(U16B-E)") (class "Default")
      (node (ref "R190") (pin "1") (pinfunction "1_1") (pintype "passive"))
      (node (ref "U16") (pin "3") (pinfunction "E_3") (pintype "passive"))
    )
    (net (code "104") (name "POWER_GND") (class "Default")
      (node (ref "C100") (pin "2") (pinfunction "2_2") (pintype "passive"))
      (node (ref "C101") (pin "2") (pinfunction "2_2") (pintype "passive"))
      (node (ref "C102") (pin "2") (pinfunction "2_2") (pintype "passive"))
      (node (ref "C103") (pin "2") (pinfunction "2_2") (pintype "passive"))
      (node (ref "C104") (pin "2") (pinfunction "2_2") (pintype "passive"))
      (node (ref "C108") (pin "2") (pinfunction "2_2") (pintype "passive"))
      (node (ref "C110") (pin "2") (pinfunction "2_2") (pintype "passive"))
      (node (ref "C111") (pin "2") (pinfunction "2_2") (pintype "passive"))
      (node (ref "C112") (pin "2") (pinfunction "2_2") (pintype "passive"))
      (node (ref "C115") (pin "2") (pinfunction "2_2") (pintype "passive"))
      (node (ref "C117") (pin "2") (pinfunction "2_2") (pintype "passive"))
      (node (ref "C62") (pin "1") (pinfunction "1_1") (pintype "passive"))
      (node (ref "C68") (pin "2") (pinfunction "2_2") (pintype "passive"))
      (node (ref "C69") (pin "2") (pinfunction "2_2") (pintype "passive"))
      (node (ref "C70") (pin "2") (pinfunction "2_2") (pintype "passive"))
      (node (ref "C71") (pin "1") (pinfunction "1_1") (pintype "passive"))
      (node (ref "C80") (pin "2") (pinfunction "2_2") (pintype "passive"))
      (node (ref "C81") (pin "2") (pinfunction "2_2") (pintype "passive"))
      (node (ref "C82") (pin "2") (pinfunction "2_2") (pintype "passive"))
      (node (ref "C96") (pin "2") (pinfunction "2_2") (pintype "passive"))
      (node (ref "C97") (pin "2") (pinfunction "2_2") (pintype "passive"))
      (node (ref "D28") (pin "1") (pinfunction "A_1") (pintype "passive"))
      (node (ref "Q28") (pin "3") (pinfunction "PS_3") (pintype "passive"))
      (node (ref "Q28") (pin "4") (pinfunction "PS_4") (pintype "passive"))
      (node (ref "Q28") (pin "5") (pinfunction "PS_5") (pintype "passive"))
      (node (ref "Q28") (pin "6") (pinfunction "PS_6") (pintype "passive"))
      (node (ref "Q28") (pin "7") (pinfunction "PS_7") (pintype "passive"))
      (node (ref "Q28") (pin "8") (pinfunction "PS_8") (pintype "passive"))
      (node (ref "Q34") (pin "3") (pinfunction "PS_3") (pintype "passive"))
      (node (ref "Q34") (pin "4") (pinfunction "PS_4") (pintype "passive"))
      (node (ref "Q34") (pin "5") (pinfunction "PS_5") (pintype "passive"))
      (node (ref "Q34") (pin "6") (pinfunction "PS_6") (pintype "passive"))
      (node (ref "Q34") (pin "7") (pinfunction "PS_7") (pintype "passive"))
      (node (ref "Q34") (pin "8") (pinfunction "PS_8") (pintype "passive"))
      (node (ref "Q41") (pin "2") (pinfunction "S_2") (pintype "passive"))
      (node (ref "Q43") (pin "2") (pinfunction "S_2") (pintype "passive"))
      (node (ref "Q45") (pin "2") (pinfunction "S_2") (pintype "passive"))
      (node (ref "Q46") (pin "3") (pinfunction "A_3") (pintype "passive"))
      (node (ref "R136") (pin "2") (pinfunction "2_2") (pintype "passive"))
      (node (ref "R169") (pin "1") (pinfunction "1_1") (pintype "passive"))
      (node (ref "R173") (pin "1") (pinfunction "1_1") (pintype "passive"))
      (node (ref "R175") (pin "1") (pinfunction "1_1") (pintype "passive"))
      (node (ref "R176") (pin "1") (pinfunction "1_1") (pintype "passive"))
      (node (ref "R177") (pin "1") (pinfunction "1_1") (pintype "passive"))
      (node (ref "R189") (pin "2") (pinfunction "2_2") (pintype "passive"))
      (node (ref "R191") (pin "2") (pinfunction "2_2") (pintype "passive"))
      (node (ref "R201") (pin "2") (pinfunction "2_2") (pintype "passive"))
      (node (ref "R203") (pin "2") (pinfunction "2_2") (pintype "passive"))
      (node (ref "R204") (pin "2") (pinfunction "2_2") (pintype "passive"))
      (node (ref "R211") (pin "2") (pinfunction "2_2") (pintype "passive"))
      (node (ref "R212") (pin "2") (pinfunction "2_2") (pintype "passive"))
      (node (ref "R213") (pin "2") (pinfunction "2_2") (pintype "passive"))
      (node (ref "R215") (pin "2") (pinfunction "2_2") (pintype "passive"))
      (node (ref "R228") (pin "2") (pinfunction "2_2") (pintype "passive"))
      (node (ref "R230") (pin "2") (pinfunction "2_2") (pintype "passive"))
      (node (ref "U10") (pin "3") (pinfunction "SGND_3") (pintype "passive"))
      (node (ref "U13") (pin "3") (pinfunction "E_3") (pintype "passive"))
      (node (ref "U14") (pin "5") (pinfunction "GND_5") (pintype "passive"))
      (node (ref "U15") (pin "2") (pinfunction "C_2") (pintype "passive"))
      (node (ref "U9") (pin "3") (pinfunction "SGND_3") (pintype "passive"))
    )
    (net (code "105") (name "SGND") (class "Default")
      (node (ref "C105") (pin "2") (pinfunction "2_2") (pintype "passive"))
      (node (ref "C106") (pin "2") (pinfunction "2_2") (pintype "passive"))
      (node (ref "C109") (pin "2") (pinfunction "2_2") (pintype "passive"))
      (node (ref "C113") (pin "1") (pinfunction "1_1") (pintype "passive"))
      (node (ref "C114") (pin "1") (pinfunction "1_1") (pintype "passive"))
      (node (ref "C66") (pin "2") (pinfunction "2_2") (pintype "passive"))
      (node (ref "C73") (pin "2") (pinfunction "2_2") (pintype "passive"))
      (node (ref "C83") (pin "2") (pinfunction "2_2") (pintype "passive"))
      (node (ref "C84") (pin "2") (pinfunction "2_2") (pintype "passive"))
      (node (ref "C85") (pin "2") (pinfunction "2_2") (pintype "passive"))
      (node (ref "C86") (pin "2") (pinfunction "2_2") (pintype "passive"))
      (node (ref "C87") (pin "2") (pinfunction "2_2") (pintype "passive"))
      (node (ref "C88") (pin "2") (pinfunction "2_2") (pintype "passive"))
      (node (ref "C89") (pin "2") (pinfunction "2_2") (pintype "passive"))
      (node (ref "C90") (pin "2") (pinfunction "2_2") (pintype "passive"))
      (node (ref "C91") (pin "2") (pinfunction "2_2") (pintype "passive"))
      (node (ref "C92") (pin "2") (pinfunction "2_2") (pintype "passive"))
      (node (ref "D26") (pin "1") (pinfunction "A_1") (pintype "passive"))
      (node (ref "D33") (pin "1") (pinfunction "A_1") (pintype "passive"))
      (node (ref "Q25") (pin "1") (pinfunction "S_1") (pintype "passive"))
      (node (ref "Q25") (pin "2") (pinfunction "S_2") (pintype "passive"))
      (node (ref "Q25") (pin "3") (pinfunction "S_3") (pintype "passive"))
      (node (ref "Q26") (pin "1") (pinfunction "S_1") (pintype "passive"))
      (node (ref "Q26") (pin "2") (pinfunction "S_2") (pintype "passive"))
      (node (ref "Q26") (pin "3") (pinfunction "S_3") (pintype "passive"))
      (node (ref "Q29") (pin "1") (pinfunction "S_1") (pintype "passive"))
      (node (ref "Q29") (pin "2") (pinfunction "S_2") (pintype "passive"))
      (node (ref "Q29") (pin "3") (pinfunction "S_3") (pintype "passive"))
      (node (ref "Q30") (pin "1") (pinfunction "S_1") (pintype "passive"))
      (node (ref "Q30") (pin "2") (pinfunction "S_2") (pintype "passive"))
      (node (ref "Q30") (pin "3") (pinfunction "S_3") (pintype "passive"))
      (node (ref "Q31") (pin "2") (pinfunction "S_2") (pintype "passive"))
      (node (ref "Q35") (pin "2") (pinfunction "S_2") (pintype "passive"))
      (node (ref "Q36") (pin "2") (pinfunction "S_2") (pintype "passive"))
      (node (ref "Q37") (pin "2") (pinfunction "E_2") (pintype "passive"))
      (node (ref "Q38") (pin "2") (pinfunction "S_2") (pintype "passive"))
      (node (ref "Q42") (pin "2") (pinfunction "S_2") (pintype "passive"))
      (node (ref "Q44") (pin "3") (pinfunction "A_3") (pintype "passive"))
      (node (ref "Q47") (pin "2") (pinfunction "E_2") (pintype "passive"))
      (node (ref "Q48") (pin "2") (pinfunction "S_2") (pintype "passive"))
      (node (ref "R116") (pin "2") (pinfunction "2_2") (pintype "passive"))
      (node (ref "R117") (pin "2") (pinfunction "2_2") (pintype "passive"))
      (node (ref "R122") (pin "1") (pinfunction "1_1") (pintype "passive"))
      (node (ref "R123") (pin "1") (pinfunction "1_1") (pintype "passive"))
      (node (ref "R124") (pin "1") (pinfunction "1_1") (pintype "passive"))
      (node (ref "R125") (pin "1") (pinfunction "1_1") (pintype "passive"))
      (node (ref "R126") (pin "1") (pinfunction "1_1") (pintype "passive"))
      (node (ref "R127") (pin "1") (pinfunction "1_1") (pintype "passive"))
      (node (ref "R128") (pin "1") (pinfunction "1_1") (pintype "passive"))
      (node (ref "R129") (pin "1") (pinfunction "1_1") (pintype "passive"))
      (node (ref "R130") (pin "1") (pinfunction "1_1") (pintype "passive"))
      (node (ref "R131") (pin "1") (pinfunction "1_1") (pintype "passive"))
      (node (ref "R132") (pin "1") (pinfunction "1_1") (pintype "passive"))
      (node (ref "R133") (pin "1") (pinfunction "1_1") (pintype "passive"))
      (node (ref "R134") (pin "2") (pinfunction "2_2") (pintype "passive"))
      (node (ref "R135") (pin "2") (pinfunction "2_2") (pintype "passive"))
      (node (ref "R158") (pin "2") (pinfunction "2_2") (pintype "passive"))
      (node (ref "R174") (pin "2") (pinfunction "2_2") (pintype "passive"))
      (node (ref "R182") (pin "2") (pinfunction "2_2") (pintype "passive"))
      (node (ref "R199") (pin "2") (pinfunction "2_2") (pintype "passive"))
      (node (ref "R202") (pin "1") (pinfunction "1_1") (pintype "passive"))
      (node (ref "R209") (pin "1") (pinfunction "1_1") (pintype "passive"))
      (node (ref "R218") (pin "1") (pinfunction "1_1") (pintype "passive"))
      (node (ref "R220") (pin "1") (pinfunction "1_1") (pintype "passive"))
      (node (ref "U11") (pin "2") (pinfunction "GND_2") (pintype "passive"))
      (node (ref "U11") (pin "4") (pinfunction "SSB_4") (pintype "passive"))
      (node (ref "U11") (pin "5") (pinfunction "SSA_5") (pintype "passive"))
      (node (ref "U11") (pin "9") (pinfunction "EP_9") (pintype "passive"))
      (node (ref "U12") (pin "2") (pinfunction "GND_2") (pintype "passive"))
    )
    (net (code "106") (name "VCC3") (class "Default")
      (node (ref "C103") (pin "1") (pinfunction "1_1") (pintype "passive"))
      (node (ref "D18") (pin "1") (pinfunction "A_1") (pintype "passive"))
      (node (ref "Q39") (pin "2") (pinfunction "E_2") (pintype "passive"))
      (node (ref "R186") (pin "1") (pinfunction "1_1") (pintype "passive"))
      (node (ref "R194") (pin "1") (pinfunction "1_1") (pintype "passive"))
      (node (ref "U16") (pin "4") (pinfunction "C_4") (pintype "passive"))
    )
    (net (code "107") (name "VCC_GD") (class "Default")
      (node (ref "C62") (pin "2") (pinfunction "2_2") (pintype "passive"))
      (node (ref "C65") (pin "1") (pinfunction "1_1") (pintype "passive"))
      (node (ref "C68") (pin "1") (pinfunction "1_1") (pintype "passive"))
      (node (ref "C71") (pin "2") (pinfunction "2_2") (pintype "passive"))
      (node (ref "C78") (pin "1") (pinfunction "1_1") (pintype "passive"))
      (node (ref "C80") (pin "1") (pinfunction "1_1") (pintype "passive"))
      (node (ref "C96") (pin "1") (pinfunction "1_1") (pintype "passive"))
      (node (ref "C97") (pin "1") (pinfunction "1_1") (pintype "passive"))
      (node (ref "D16") (pin "1") (pinfunction "A_1") (pintype "passive"))
      (node (ref "D21") (pin "1") (pinfunction "A_1") (pintype "passive"))
      (node (ref "Q39") (pin "3") (pinfunction "C_3") (pintype "passive"))
      (node (ref "U10") (pin "7") (pinfunction "VCC_7") (pintype "passive"))
      (node (ref "U9") (pin "7") (pinfunction "VCC_7") (pintype "passive"))
    )
    (net (code "108") (name "VCC_IC") (class "Default")
      (node (ref "C108") (pin "1") (pinfunction "1_1") (pintype "passive"))
      (node (ref "D18") (pin "2") (pinfunction "K_2") (pintype "passive"))
      (node (ref "U14") (pin "4") (pinfunction "VCC_4") (pintype "passive"))
    )
    (net (code "109") (name "VRECT_NEG") (class "Default")
      (node (ref "BD2") (pin "4") (pinfunction "4_4") (pintype "passive"))
      (node (ref "C61") (pin "1") (pinfunction "1_1") (pintype "passive"))
      (node (ref "D27") (pin "2") (pinfunction "K_2") (pintype "passive"))
      (node (ref "R169") (pin "2") (pinfunction "2_2") (pintype "passive"))
      (node (ref "R173") (pin "2") (pinfunction "2_2") (pintype "passive"))
      (node (ref "R175") (pin "2") (pinfunction "2_2") (pintype "passive"))
      (node (ref "R176") (pin "2") (pinfunction "2_2") (pintype "passive"))
      (node (ref "R177") (pin "2") (pinfunction "2_2") (pintype "passive"))
      (node (ref "R226") (pin "1") (pinfunction "1_1") (pintype "passive"))
    )
    (net (code "110") (name "VRECT_POS") (class "Default")
      (node (ref "BD2") (pin "1") (pinfunction "1_1") (pintype "passive"))
      (node (ref "C115") (pin "1") (pinfunction "1_1") (pintype "passive"))
      (node (ref "C117") (pin "1") (pinfunction "1_1") (pintype "passive"))
      (node (ref "C61") (pin "2") (pinfunction "2_2") (pintype "passive"))
      (node (ref "Q27") (pin "TAP") (pinfunction "D_TAP") (pintype "passive"))
      (node (ref "Q32") (pin "TAP") (pinfunction "D_TAP") (pintype "passive"))
    )
    (net (code "111") (name "unconnected-(U9-NC-Pad4)") (class "Default")
      (node (ref "U9") (pin "4") (pinfunction "NC_4") (pintype "passive+no_connect"))
    )
    (net (code "112") (name "unconnected-(U9-NC-Pad8)") (class "Default")
      (node (ref "U9") (pin "8") (pinfunction "NC_8") (pintype "passive+no_connect"))
    )
    (net (code "113") (name "unconnected-(U9-NC-Pad9)") (class "Default")
      (node (ref "U9") (pin "9") (pinfunction "NC_9") (pintype "passive+no_connect"))
    )
    (net (code "114") (name "unconnected-(U9-NC-Pad10)") (class "Default")
      (node (ref "U9") (pin "10") (pinfunction "NC_10") (pintype "passive+no_connect"))
    )
    (net (code "115") (name "unconnected-(U9-NC-Pad14)") (class "Default")
      (node (ref "U9") (pin "14") (pinfunction "NC_14") (pintype "passive+no_connect"))
    )
    (net (code "116") (name "unconnected-(U10-NC-Pad4)") (class "Default")
      (node (ref "U10") (pin "4") (pinfunction "NC_4") (pintype "passive+no_connect"))
    )
    (net (code "117") (name "unconnected-(U10-NC-Pad8)") (class "Default")
      (node (ref "U10") (pin "8") (pinfunction "NC_8") (pintype "passive+no_connect"))
    )
    (net (code "118") (name "unconnected-(U10-NC-Pad9)") (class "Default")
      (node (ref "U10") (pin "9") (pinfunction "NC_9") (pintype "passive+no_connect"))
    )
    (net (code "119") (name "unconnected-(U10-NC-Pad10)") (class "Default")
      (node (ref "U10") (pin "10") (pinfunction "NC_10") (pintype "passive+no_connect"))
    )
    (net (code "120") (name "unconnected-(U10-NC-Pad14)") (class "Default")
      (node (ref "U10") (pin "14") (pinfunction "NC_14") (pintype "passive+no_connect"))
    )
    (net (code "121") (name "unconnected-(U14-NC-Pad2)") (class "Default")
      (node (ref "U14") (pin "2") (pinfunction "NC_2") (pintype "passive+no_connect"))
    )
  )
)
